# PT_SAT_Simplex.net
KiCad netlist of a schematic drawn in Altium Designer
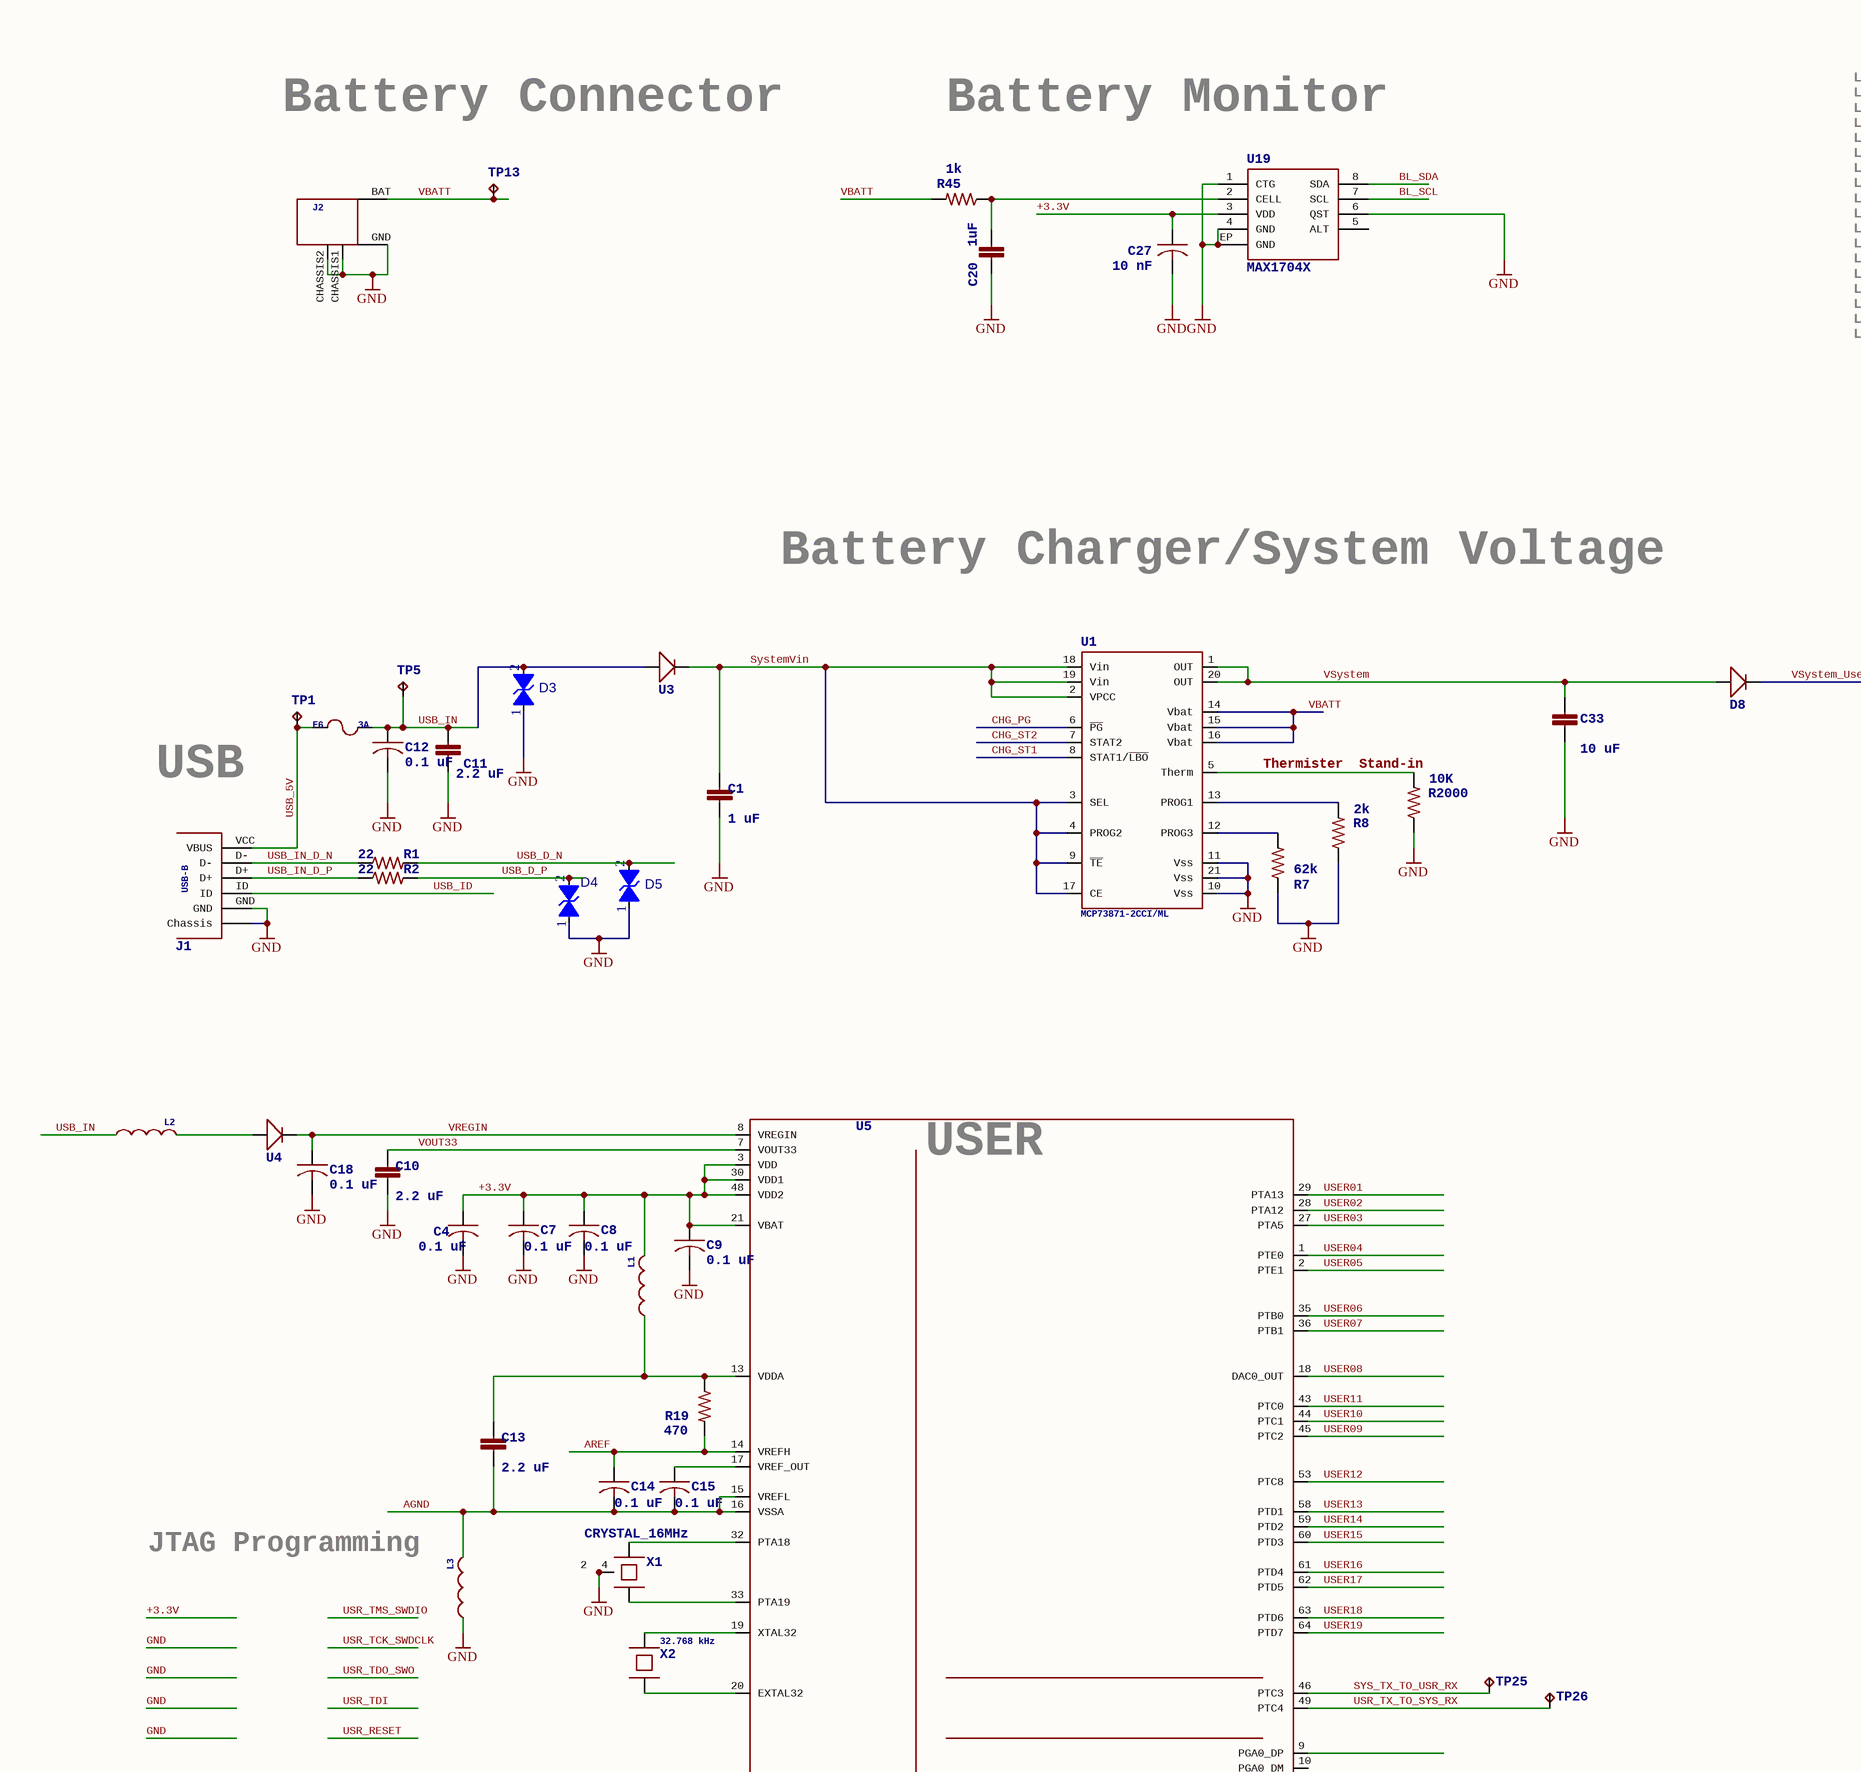
[diagram p0: PT_SAT_Simplex.SchDoc, top left]
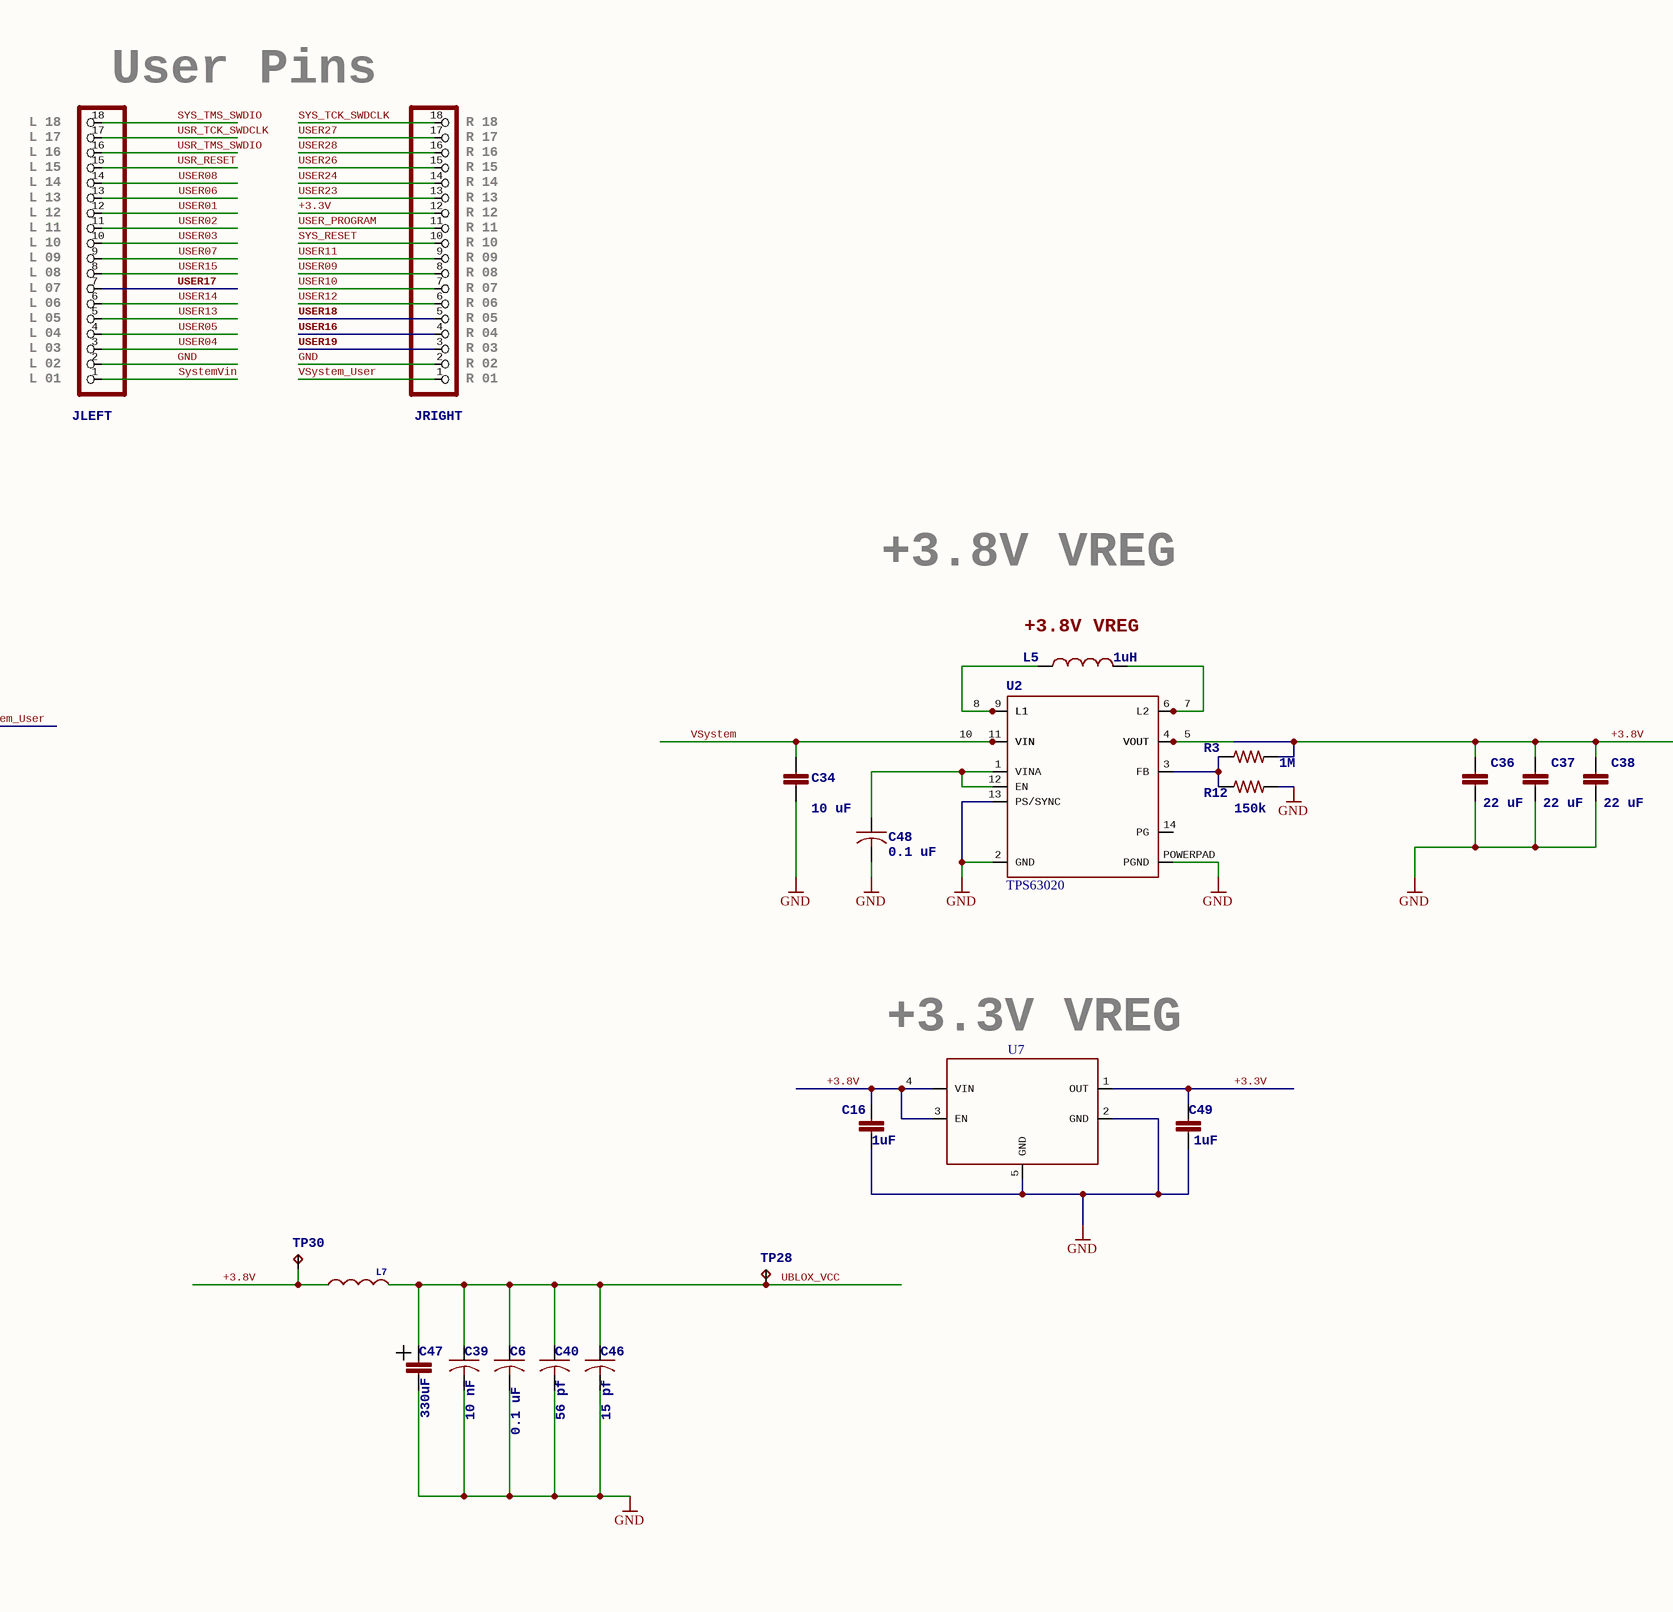
[diagram p1: PT_SAT_Simplex.SchDoc, top middle]
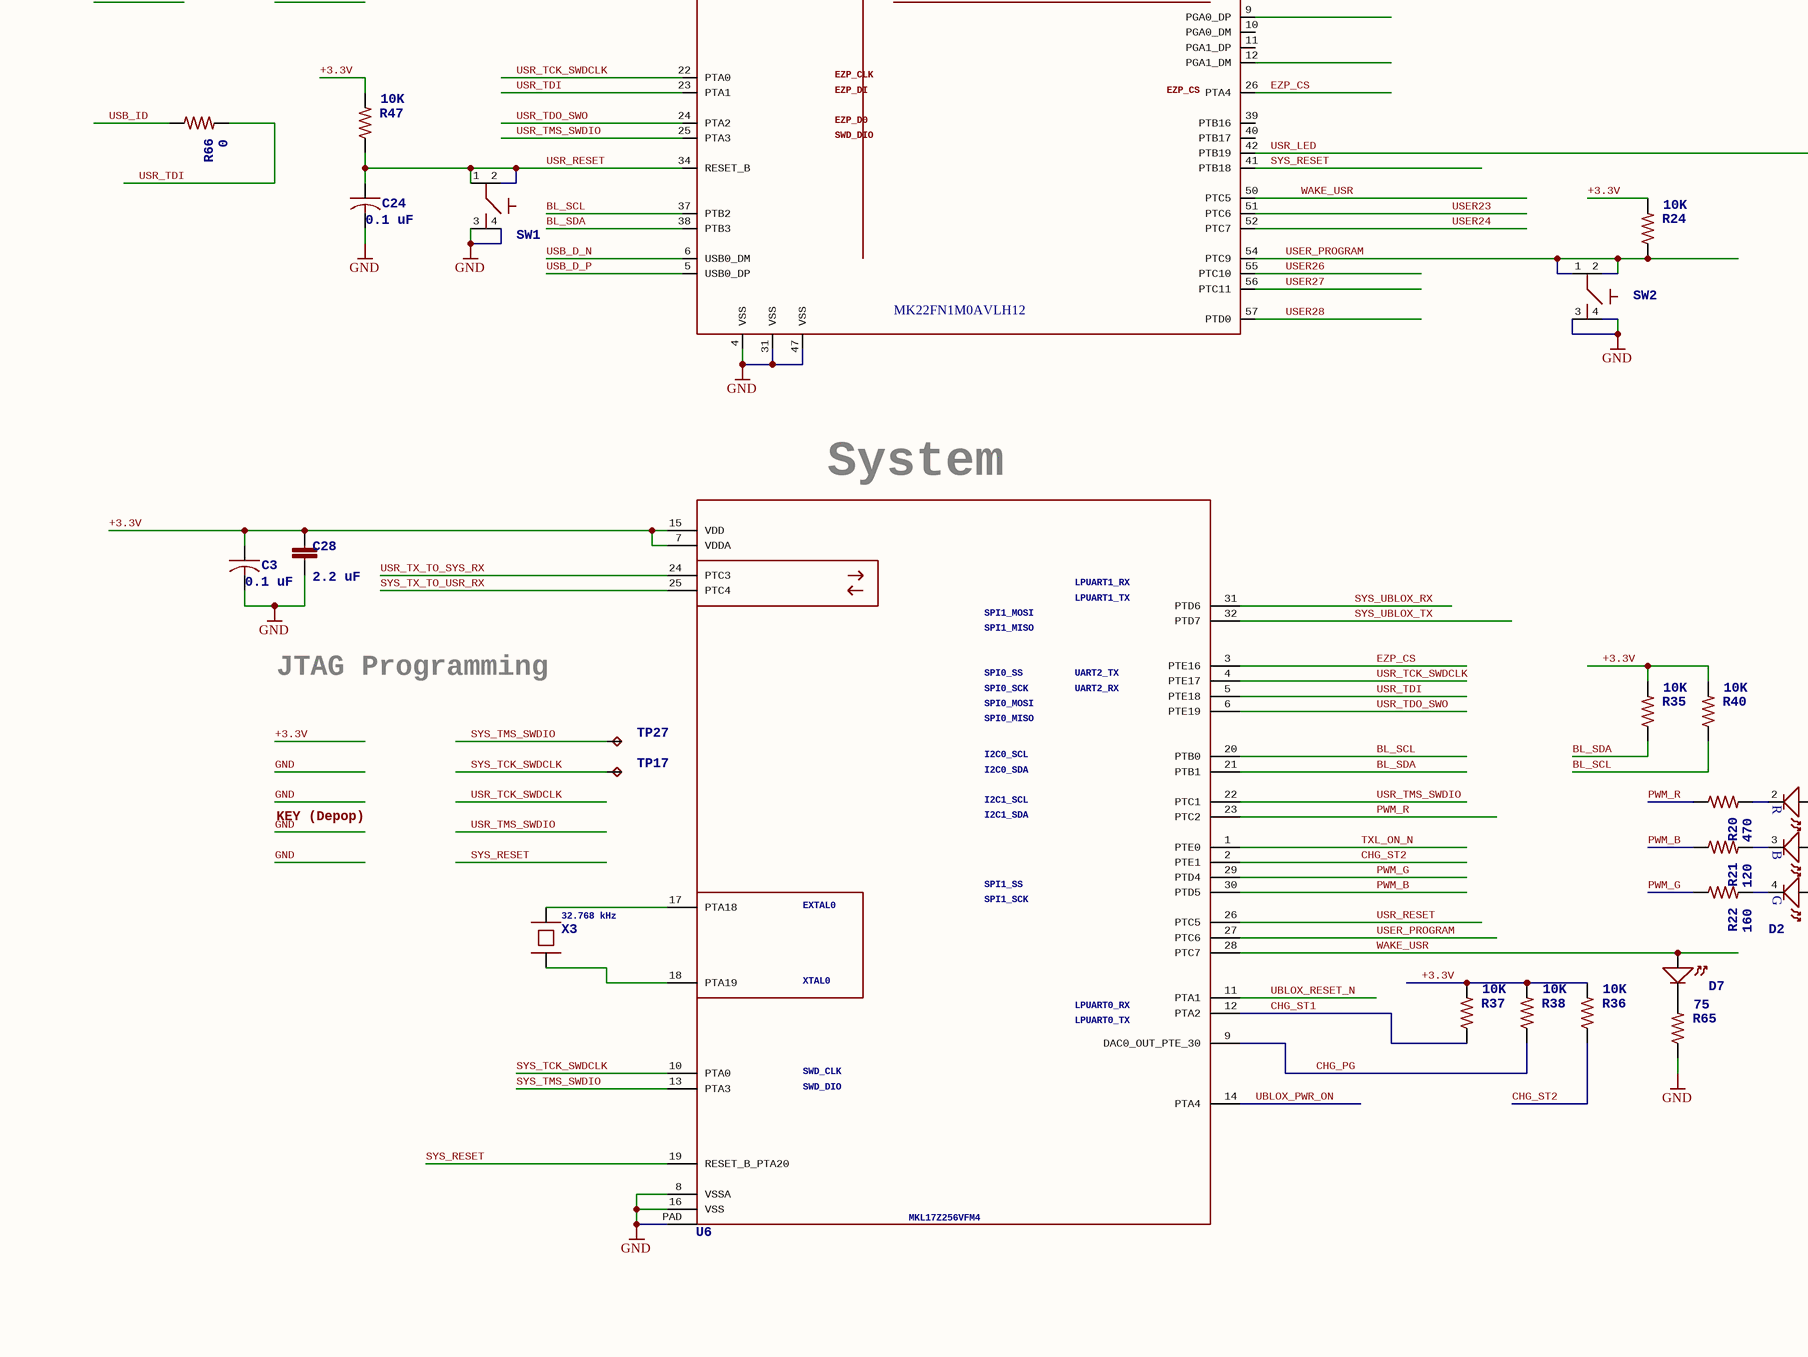
[diagram p2: PT_SAT_Simplex.SchDoc, bottom left]
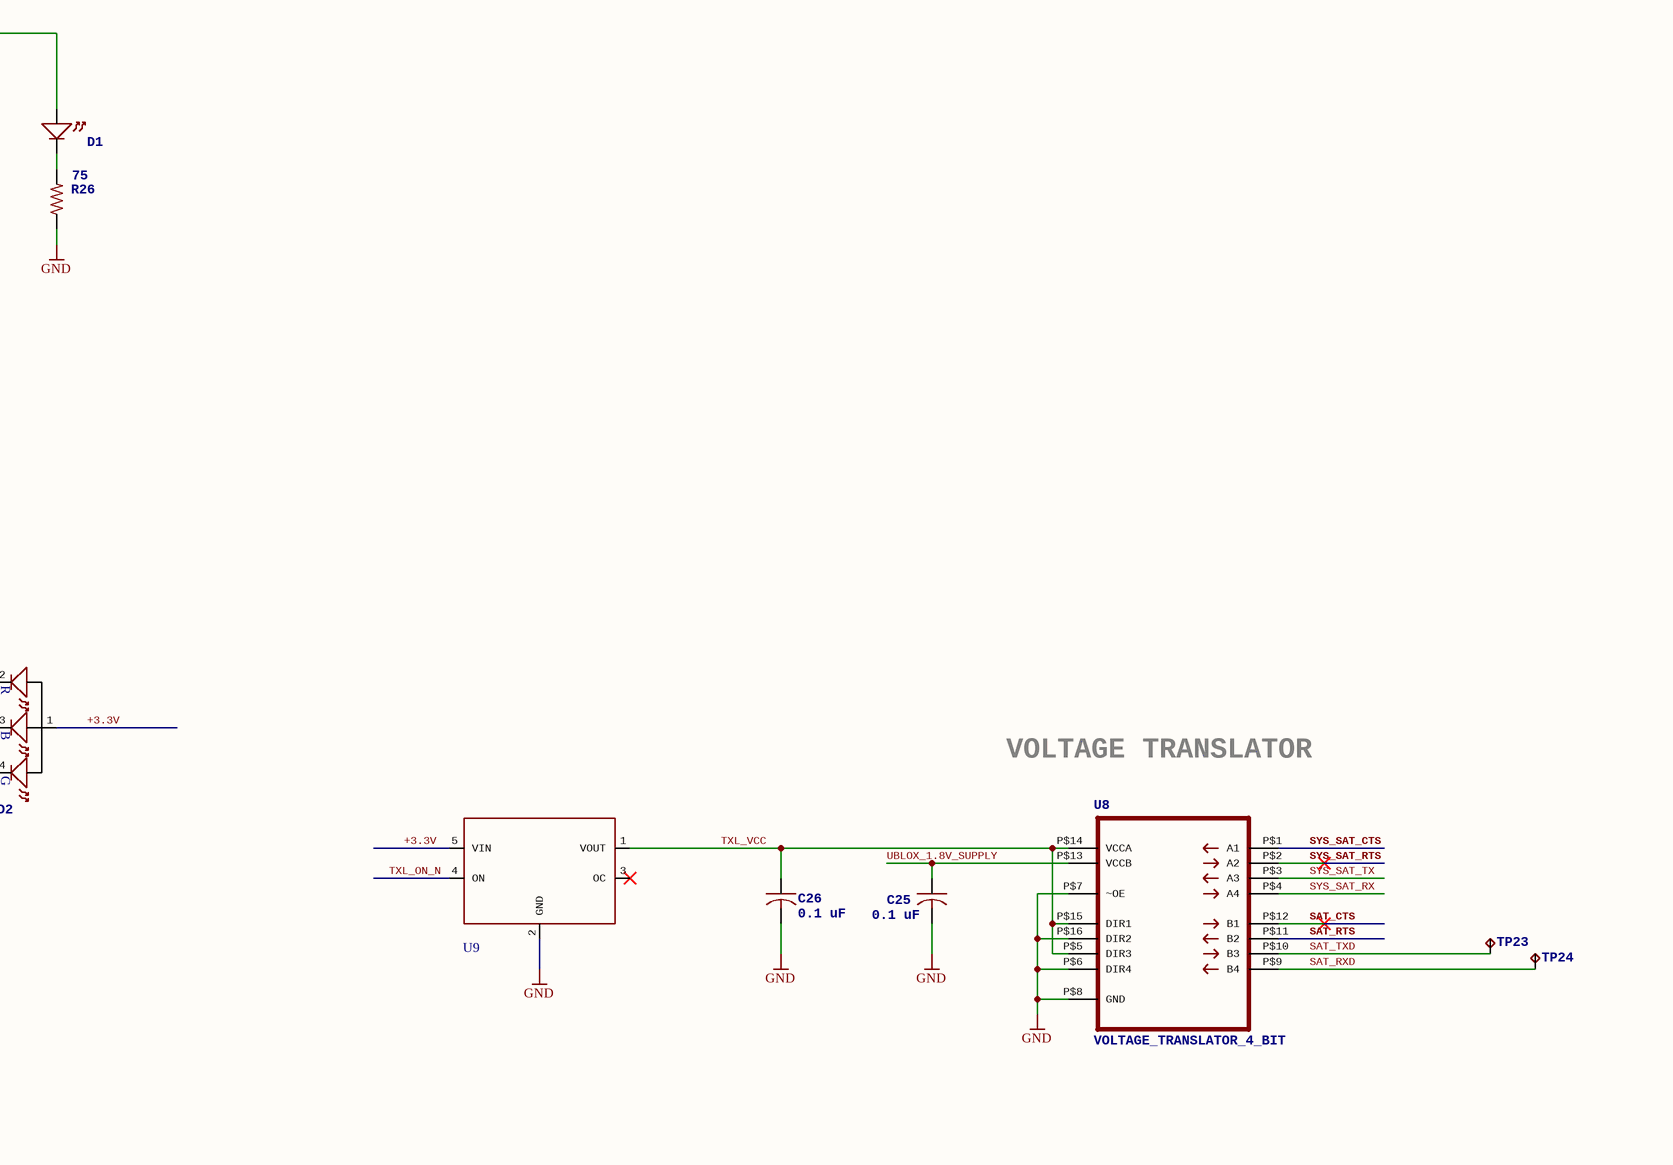
[diagram p3: PT_SAT_Simplex.SchDoc, bottom middle]
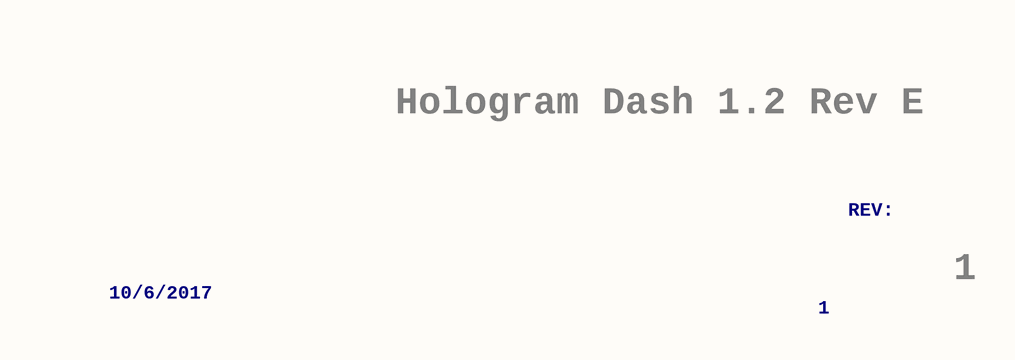
[diagram p4: PT_SAT_Simplex.SchDoc, bottom right]

(export (version "E")
  (design (tool "Eeschema 10.0.6"))
  (components
    (comp (ref "C1")
      (value "1 uF")
      (footprint "KON-SU260:CAP0603")
      (description "Capacitor, 1 uF, 0603")
      (fields (field (name "MPN") "GRM188R71C105KA12D") (field (name "MFG") "MURATA"))
      (libsource (lib "KON-SU260") (part "CAP1uF_0603"))
    )
    (comp (ref "C3")
      (value "0.1 uF")
      (footprint "KON-SU260:CAP0402")
      (description "CAPACITOR, 0.1 uF, 0402")
      (fields (field (name "MFG") "MURATA") (field (name "MPN") "GRM155R61C104KA88D"))
      (libsource (lib "KON-SU260") (part "CAP0.1uF_0402"))
    )
    (comp (ref "C4")
      (value "0.1 uF")
      (footprint "KON-SU260:CAP0402")
      (description "CAPACITOR, 0.1 uF, 0402")
      (fields (field (name "MFG") "MURATA") (field (name "MPN") "GRM155R61C104KA88D"))
      (libsource (lib "KON-SU260") (part "CAP0.1uF_0402"))
    )
    (comp (ref "C6")
      (value "0.1 uF")
      (footprint "KON-SU260:CAP0402")
      (description "CAPACITOR, 0.1 uF, 0402")
      (fields (field (name "MFG") "MURATA") (field (name "MPN") "GRM155R61C104KA88D"))
      (libsource (lib "KON-SU260") (part "CAP0.1uF_0402"))
    )
    (comp (ref "C7")
      (value "0.1 uF")
      (footprint "KON-SU260:CAP0402")
      (description "CAPACITOR, 0.1 uF, 0402")
      (fields (field (name "MFG") "MURATA") (field (name "MPN") "GRM155R61C104KA88D"))
      (libsource (lib "KON-SU260") (part "CAP0.1uF_0402"))
    )
    (comp (ref "C8")
      (value "0.1 uF")
      (footprint "KON-SU260:CAP0402")
      (description "CAPACITOR, 0.1 uF, 0402")
      (fields (field (name "MFG") "MURATA") (field (name "MPN") "GRM155R61C104KA88D"))
      (libsource (lib "KON-SU260") (part "CAP0.1uF_0402"))
    )
    (comp (ref "C9")
      (value "0.1 uF")
      (footprint "KON-SU260:CAP0402")
      (description "CAPACITOR, 0.1 uF, 0402")
      (fields (field (name "MFG") "MURATA") (field (name "MPN") "GRM155R61C104KA88D"))
      (libsource (lib "KON-SU260") (part "CAP0.1uF_0402"))
    )
    (comp (ref "C10")
      (value "2.2 uF")
      (footprint "KON-SU260:CAP0603")
      (description "Capacitor, 2.2 uF, 0603")
      (fields (field (name "MPN") "CL10A225MQ8NNNC") (field (name "MFG") "SAMSUNG"))
      (libsource (lib "KON-SU260") (part "CAP2.2uF_0603"))
    )
    (comp (ref "C11")
      (value "2.2 uF")
      (footprint "KON-SU260:CAP0603")
      (description "Capacitor, 2.2 uF, 0603")
      (fields (field (name "MPN") "CL10A225MQ8NNNC") (field (name "MFG") "SAMSUNG"))
      (libsource (lib "KON-SU260") (part "CAP2.2uF_0603"))
    )
    (comp (ref "C12")
      (value "0.1 uF")
      (footprint "KON-SU260:CAP0402")
      (description "CAPACITOR, 0.1 uF, 0402")
      (fields (field (name "MFG") "MURATA") (field (name "MPN") "GRM155R61C104KA88D"))
      (libsource (lib "KON-SU260") (part "CAP0.1uF_0402"))
    )
    (comp (ref "C13")
      (value "2.2 uF")
      (footprint "KON-SU260:CAP0603")
      (description "Capacitor, 2.2 uF, 0603")
      (fields (field (name "MPN") "CL10A225MQ8NNNC") (field (name "MFG") "SAMSUNG"))
      (libsource (lib "KON-SU260") (part "CAP2.2uF_0603"))
    )
    (comp (ref "C14")
      (value "0.1 uF")
      (footprint "KON-SU260:CAP0402")
      (description "CAPACITOR, 0.1 uF, 0402")
      (fields (field (name "MFG") "MURATA") (field (name "MPN") "GRM155R61C104KA88D"))
      (libsource (lib "KON-SU260") (part "CAP0.1uF_0402"))
    )
    (comp (ref "C15")
      (value "0.1 uF")
      (footprint "KON-SU260:CAP0402")
      (description "CAPACITOR, 0.1 uF, 0402")
      (fields (field (name "MFG") "MURATA") (field (name "MPN") "GRM155R61C104KA88D"))
      (libsource (lib "KON-SU260") (part "CAP0.1uF_0402"))
    )
    (comp (ref "C16")
      (value "1uF")
      (footprint "KON-SU260:CAP0402")
      (description "CAPACITOR, 1uF, 0402")
      (fields (field (name "MPN") "04026D105KAT2A") (field (name "MFG") "AVX"))
      (libsource (lib "KON-SU260") (part "CAP1uF_0402"))
    )
    (comp (ref "C18")
      (value "0.1 uF")
      (footprint "KON-SU260:CAP0402")
      (description "CAPACITOR, 0.1 uF, 0402")
      (fields (field (name "MFG") "MURATA") (field (name "MPN") "GRM155R61C104KA88D"))
      (libsource (lib "KON-SU260") (part "CAP0.1uF_0402"))
    )
    (comp (ref "C20")
      (value "1uF")
      (footprint "KON-SU260:CAP0402")
      (description "CAPACITOR, 1uF, 0402")
      (fields (field (name "MPN") "04026D105KAT2A") (field (name "MFG") "AVX"))
      (libsource (lib "KON-SU260") (part "CAP1uF_0402"))
    )
    (comp (ref "C24")
      (value "0.1 uF")
      (footprint "KON-SU260:CAP0402")
      (description "CAPACITOR, 0.1 uF, 0402")
      (fields (field (name "MFG") "MURATA") (field (name "MPN") "GRM155R61C104KA88D"))
      (libsource (lib "KON-SU260") (part "CAP0.1uF_0402"))
    )
    (comp (ref "C25")
      (value "0.1 uF")
      (footprint "KON-SU260:CAP0402")
      (description "CAPACITOR, 0.1 uF, 0402")
      (fields (field (name "MFG") "MURATA") (field (name "MPN") "GRM155R61C104KA88D"))
      (libsource (lib "KON-SU260") (part "CAP0.1uF_0402"))
    )
    (comp (ref "C26")
      (value "0.1 uF")
      (footprint "KON-SU260:CAP0402")
      (description "CAPACITOR, 0.1 uF, 0402")
      (fields (field (name "MFG") "MURATA") (field (name "MPN") "GRM155R61C104KA88D"))
      (libsource (lib "KON-SU260") (part "CAP0.1uF_0402"))
    )
    (comp (ref "C27")
      (value "10 nF")
      (footprint "KON-SU260:CAP0402")
      (description "CAPACITOR, 10 nF, 0402")
      (fields (field (name "MFG") "MURATA") (field (name "MPN") "GRM155R71C103KA01D"))
      (libsource (lib "KON-SU260") (part "CAP10nF_0402"))
    )
    (comp (ref "C28")
      (value "2.2 uF")
      (footprint "KON-SU260:CAP0603")
      (description "Capacitor, 2.2 uF, 0603")
      (fields (field (name "MPN") "CL10A225MQ8NNNC") (field (name "MFG") "SAMSUNG"))
      (libsource (lib "KON-SU260") (part "CAP2.2uF_0603"))
    )
    (comp (ref "C33")
      (value "10 uF")
      (footprint "KON-SU260:CAP0603")
      (description "Capacitor, 10 uF, 0603")
      (fields (field (name "MPN") "GRM188R60J106ME84D") (field (name "MFG") "Murata"))
      (libsource (lib "KON-SU260") (part "CAP10uF_0603"))
    )
    (comp (ref "C34")
      (value "10 uF")
      (footprint "KON-SU260:CAP0603")
      (description "Capacitor, 10 uF, 0603")
      (fields (field (name "MPN") "GRM188R60J106ME84D") (field (name "MFG") "Murata"))
      (libsource (lib "KON-SU260") (part "CAP10uF_0603"))
    )
    (comp (ref "C36")
      (value "22 uF")
      (footprint "KON-SU260:CAP0603")
      (description "Capacitor, 22 uF, 0603")
      (fields (field (name "MPN") "GRM188R60J226MEA0D") (field (name "MFG") "MURATA"))
      (libsource (lib "KON-SU260") (part "CAP22uF_0603"))
    )
    (comp (ref "C37")
      (value "22 uF")
      (footprint "KON-SU260:CAP0603")
      (description "Capacitor, 22 uF, 0603")
      (fields (field (name "MPN") "GRM188R60J226MEA0D") (field (name "MFG") "MURATA"))
      (libsource (lib "KON-SU260") (part "CAP22uF_0603"))
    )
    (comp (ref "C38")
      (value "22 uF")
      (footprint "KON-SU260:CAP0603")
      (description "Capacitor, 22 uF, 0603")
      (fields (field (name "MPN") "GRM188R60J226MEA0D") (field (name "MFG") "MURATA"))
      (libsource (lib "KON-SU260") (part "CAP22uF_0603"))
    )
    (comp (ref "C39")
      (value "10 nF")
      (footprint "KON-SU260:CAP0402")
      (description "CAPACITOR, 10 nF, 0402")
      (fields (field (name "MFG") "MURATA") (field (name "MPN") "GRM155R71C103KA01D"))
      (libsource (lib "KON-SU260") (part "CAP10nF_0402"))
    )
    (comp (ref "C40")
      (value "56 pf")
      (footprint "KON-SU260:CAP0402")
      (description "CAPACITOR, 56 pF, 0402")
      (fields (field (name "MFG") "KEMET") (field (name "MPN") "C0402C560J5GACTU"))
      (libsource (lib "KON-SU260") (part "CAP56pF_0402"))
    )
    (comp (ref "C46")
      (value "15 pf")
      (footprint "KON-SU260:CAP0402")
      (description "CAPACITOR, 15 pF, 0402")
      (fields (field (name "MFG") "AVX/ELCO") (field (name "MPN") "04025A150JAT2A"))
      (libsource (lib "KON-SU260") (part "CAP15pF_0402"))
    )
    (comp (ref "C47")
      (value "330uF")
      (footprint "KON-SU260:CAP1210POL")
      (description "Capacitor, 330 uF, 1210, Polarized Tantalum")
      (fields (field (name "MPN") "F950J337MBAAQ2") (field (name "MFG") "AVX"))
      (libsource (lib "KON-SU260") (part "CAP330uF_1210P"))
    )
    (comp (ref "C48")
      (value "0.1 uF")
      (footprint "KON-SU260:CAP0402")
      (description "CAPACITOR, 0.1 uF, 0402")
      (fields (field (name "MFG") "MURATA") (field (name "MPN") "GRM155R61C104KA88D"))
      (libsource (lib "KON-SU260") (part "CAP0.1uF_0402"))
    )
    (comp (ref "C49")
      (value "1uF")
      (footprint "KON-SU260:CAP0402")
      (description "CAPACITOR, 1uF, 0402")
      (fields (field (name "MPN") "04026D105KAT2A") (field (name "MFG") "AVX"))
      (libsource (lib "KON-SU260") (part "CAP1uF_0402"))
    )
    (comp (ref "D1")
      (value "LED_0402_VLMW")
      (footprint "LED_0402_VISHAY_VLMW")
      (description "LED, Vishay White 0402")
      (fields (field (name "MFG") "VISHAY") (field (name "MPN") "VLMW1500-GS08"))
      (libsource (lib "KON-SU260") (part "LED_0402_VLMW"))
    )
    (comp (ref "D2")
      (value "LED_RGB_1mm_sq")
      (footprint "LED-RGB-1X1")
      (description "LED, Tri-color, RGB, 1mm sq")
      (fields (field (name "MFG") "Rohm") (field (name "MPN") "SMLP34RGB2W3"))
      (libsource (lib "KON-SU260") (part "LED_RGB_1mm_sq"))
    )
    (comp (ref "D3")
      (value "~")
      (footprint "PESD_0402")
      (description "DIODE,ZENER VOLTAGE SUPPRESSOR,+/-14V")
      (fields (field (name "MFG") "Littlefuse") (field (name "MPN") "PESD0402-140"))
      (libsource (lib "KON-SU260") (part "PESD_14V"))
    )
    (comp (ref "D4")
      (value "~")
      (footprint "PESD_0402")
      (description "DIODE,ZENER VOLTAGE SUPPRESSOR,+/-14V")
      (fields (field (name "MFG") "Littlefuse") (field (name "MPN") "PESD0402-140"))
      (libsource (lib "KON-SU260") (part "PESD_14V"))
    )
    (comp (ref "D5")
      (value "~")
      (footprint "PESD_0402")
      (description "DIODE,ZENER VOLTAGE SUPPRESSOR,+/-14V")
      (fields (field (name "MFG") "Littlefuse") (field (name "MPN") "PESD0402-140"))
      (libsource (lib "KON-SU260") (part "PESD_14V"))
    )
    (comp (ref "D7")
      (value "LED_0402_VLMW")
      (footprint "LED_0402_VISHAY_VLMW")
      (description "LED, Vishay White 0402")
      (fields (field (name "MFG") "VISHAY") (field (name "MPN") "VLMW1500-GS08"))
      (libsource (lib "KON-SU260") (part "LED_0402_VLMW"))
    )
    (comp (ref "D8")
      (value "CDBQR0230L")
      (footprint "DIODE_0402")
      (description "Schottky Barrier Diode, 200 mA, 30 V, 0402 package")
      (fields (field (name "MFG") "Comchip"))
      (libsource (lib "KON-SU260") (part "DIODE_0402_200mA"))
    )
    (comp (ref "F6")
      (value "3A")
      (footprint "KON-SU260:RES0603")
      (description "Fuse, 3A, 0603")
      (fields (field (name "MFG") "Bourns") (field (name "MPN") "SF-0603S300-2"))
      (libsource (lib "KON-SU260") (part "FUSE_0603"))
    )
    (comp (ref "J1")
      (value "Micro USB B FCI 10118193")
      (footprint "USB_MICRO_FCI_10118193")
      (description "Connector, Micro USB B, FCI")
      (fields
        (field (name "MFG") "Amphenol FCI")
        (field (name "MPN") "10118193-0001LF")
        (field (name "USB-B") "USB-B")
      )
      (libsource (lib "KON-SU260") (part "USB_MICRO_B_FCI_10118193"))
    )
    (comp (ref "J2")
      (value "BAT_TERM_TOP_ENTRY")
      (footprint "JST-PH-2-Top")
      (description "Battery Connector JST-PH2 Top Entry")
      (fields (field (name "MPN") "B2B-PH-SM4-TB(LF)(SN)") (field (name "MFG") "JST"))
      (libsource (lib "KON-SU260") (part "BAT_TERM_TOP_ENTRY"))
    )
    (comp (ref "JLEFT")
      (value "22-28-4180")
      (footprint "KON-SU260:1X18")
      (description "Header, Male, 1x18, 0.1\"")
      (fields (field (name "MFG") "MOLEX"))
      (libsource (lib "KON-SU260") (part "PINHD-1X18"))
    )
    (comp (ref "JRIGHT")
      (value "22-28-4180")
      (footprint "KON-SU260:1X18")
      (description "Header, Male, 1x18, 0.1\"")
      (fields (field (name "MFG") "MOLEX"))
      (libsource (lib "KON-SU260") (part "PINHD-1X18"))
    )
    (comp (ref "L1")
      (value "FerriteBead_220ohm")
      (footprint "KON-SU260:RES0603")
      (description "FerriteBead, 220ohm")
      (fields (field (name "MPN") "BLM18AG121SN1D") (field (name "MFG") "Murata"))
      (libsource (lib "KON-SU260") (part "FerriteBead_220ohm"))
    )
    (comp (ref "L2")
      (value "FerriteBead_220ohm")
      (footprint "KON-SU260:RES0603")
      (description "FerriteBead, 220ohm")
      (fields (field (name "MPN") "BLM18AG121SN1D") (field (name "MFG") "Murata"))
      (libsource (lib "KON-SU260") (part "FerriteBead_220ohm"))
    )
    (comp (ref "L3")
      (value "FerriteBead_220ohm")
      (footprint "KON-SU260:RES0603")
      (description "FerriteBead, 220ohm")
      (fields (field (name "MPN") "BLM18AG121SN1D") (field (name "MFG") "Murata"))
      (libsource (lib "KON-SU260") (part "FerriteBead_220ohm"))
    )
    (comp (ref "L5")
      (value "1uH")
      (footprint "COILCRAFT_XFL4020")
      (description "Inductor, 1 uH, Coilcraft")
      (fields (field (name "MPN") "XFL4020-102MEC") (field (name "MFG") "Coilcraft"))
      (libsource (lib "KON-SU260") (part "INDUCTOR_1UH_XFL4020-102MEC"))
    )
    (comp (ref "L7")
      (value "FerriteBead_220ohm")
      (footprint "KON-SU260:RES0603")
      (description "FerriteBead, 220ohm")
      (fields (field (name "MPN") "BLM18AG121SN1D") (field (name "MFG") "Murata"))
      (libsource (lib "KON-SU260") (part "FerriteBead_220ohm"))
    )
    (comp (ref "R1")
      (value "22")
      (footprint "KON-SU260:RES0402")
      (description "Resistor, 22 ohm, 0402 case, 1%")
      (fields (field (name "MFG") "YAEGO") (field (name "MPN") "RC0402FR-0722RL"))
      (libsource (lib "KON-SU260") (part "RES22R_0402"))
    )
    (comp (ref "R2")
      (value "22")
      (footprint "KON-SU260:RES0402")
      (description "Resistor, 22 ohm, 0402 case, 1%")
      (fields (field (name "MFG") "YAEGO") (field (name "MPN") "RC0402FR-0722RL"))
      (libsource (lib "KON-SU260") (part "RES22R_0402"))
    )
    (comp (ref "R3")
      (value "1M")
      (footprint "KON-SU260:RES0402")
      (description "Resistor, 1M ohm, 0402 case, 1%")
      (fields (field (name "MFG") "YAEGO") (field (name "MPN") "RC0402FR-071ML"))
      (libsource (lib "KON-SU260") (part "RES1M_0402"))
    )
    (comp (ref "R7")
      (value "62k")
      (footprint "KON-SU260:RES0402")
      (description "Resistor, 62K ohm, 0402 case")
      (fields (field (name "MFG") "YAEGO") (field (name "MPN") "RC0402FR-0762KL"))
      (libsource (lib "KON-SU260") (part "RES62K_0402_1"))
    )
    (comp (ref "R8")
      (value "2k")
      (footprint "KON-SU260:RES0402")
      (description "Resistor, 2K ohm, 0402 case")
      (fields (field (name "MFG") "YAEGO") (field (name "MPN") "RC0402FR-072KL"))
      (libsource (lib "KON-SU260") (part "RES2K_0402"))
    )
    (comp (ref "R12")
      (value "150k")
      (footprint "KON-SU260:RES0402")
      (description "Res, 150k ohm, 0402 case, 1%")
      (fields (field (name "MFG") "YAEGO") (field (name "MPN") "RC0402FR-07150KL"))
      (libsource (lib "KON-SU260") (part "RES150K_0402"))
    )
    (comp (ref "R19")
      (value "470")
      (footprint "KON-SU260:RES0402")
      (description "Resistor, 470 ohm, 0402 case, 1%")
      (fields (field (name "MFG") "PANASONIC") (field (name "MPN") "ERJ-2GEJ471X"))
      (libsource (lib "KON-SU260") (part "RES470R_0402"))
    )
    (comp (ref "R20")
      (value "470")
      (footprint "KON-SU260:RES0402")
      (description "Resistor, 470 ohm, 0402 case, 1%")
      (fields (field (name "MFG") "PANASONIC") (field (name "MPN") "ERJ-2GEJ471X"))
      (libsource (lib "KON-SU260") (part "RES470R_0402"))
    )
    (comp (ref "R21")
      (value "120")
      (footprint "KON-SU260:RES0402")
      (description "Resistor, 120 ohm, 0402 case, 1%")
      (fields (field (name "MFG") "PANASONIC") (field (name "MPN") "ERJ-2GEJ121X"))
      (libsource (lib "KON-SU260") (part "RES120R_0402"))
    )
    (comp (ref "R22")
      (value "160")
      (footprint "KON-SU260:RES0402")
      (description "Resistor, 160 ohm, 0402 case, 1%")
      (fields (field (name "MFG") "PANASONIC") (field (name "MPN") "ERJ-2GEJ161X"))
      (libsource (lib "KON-SU260") (part "RES160R_0402"))
    )
    (comp (ref "R24")
      (value "10K")
      (footprint "KON-SU260:RES0402")
      (description "Resistor, 10k ohm, 0402")
      (fields (field (name "MFG") "YAEGO") (field (name "MPN") "RC0402JR-0710KL"))
      (libsource (lib "KON-SU260") (part "RES10K_0402"))
    )
    (comp (ref "R26")
      (value "75")
      (footprint "KON-SU260:RES0402")
      (description "Resistor, 75 ohm, 0402, 1%")
      (fields (field (name "MFG") "YAEGO") (field (name "MPN") "RC0402FR-0775RL"))
      (libsource (lib "KON-SU260") (part "RES75R_0402"))
    )
    (comp (ref "R35")
      (value "10K")
      (footprint "KON-SU260:RES0402")
      (description "Resistor, 10k ohm, 0402")
      (fields (field (name "MFG") "YAEGO") (field (name "MPN") "RC0402JR-0710KL"))
      (libsource (lib "KON-SU260") (part "RES10K_0402"))
    )
    (comp (ref "R36")
      (value "10K")
      (footprint "KON-SU260:RES0402")
      (description "Resistor, 10k ohm, 0402")
      (fields (field (name "MFG") "YAEGO") (field (name "MPN") "RC0402JR-0710KL"))
      (libsource (lib "KON-SU260") (part "RES10K_0402"))
    )
    (comp (ref "R37")
      (value "10K")
      (footprint "KON-SU260:RES0402")
      (description "Resistor, 10k ohm, 0402")
      (fields (field (name "MFG") "YAEGO") (field (name "MPN") "RC0402JR-0710KL"))
      (libsource (lib "KON-SU260") (part "RES10K_0402"))
    )
    (comp (ref "R38")
      (value "10K")
      (footprint "KON-SU260:RES0402")
      (description "Resistor, 10k ohm, 0402")
      (fields (field (name "MFG") "YAEGO") (field (name "MPN") "RC0402JR-0710KL"))
      (libsource (lib "KON-SU260") (part "RES10K_0402"))
    )
    (comp (ref "R40")
      (value "10K")
      (footprint "KON-SU260:RES0402")
      (description "Resistor, 10k ohm, 0402")
      (fields (field (name "MFG") "YAEGO") (field (name "MPN") "RC0402JR-0710KL"))
      (libsource (lib "KON-SU260") (part "RES10K_0402"))
    )
    (comp (ref "R45")
      (value "1k")
      (footprint "KON-SU260:RES0402")
      (description "Resistor, 1k, 0402 case, 1%")
      (fields (field (name "MFG") "YAEGO") (field (name "MPN") "RC0402JR-071KL"))
      (libsource (lib "KON-SU260") (part "RES1K_0402"))
    )
    (comp (ref "R47")
      (value "10K")
      (footprint "KON-SU260:RES0402")
      (description "Resistor, 10k ohm, 0402")
      (fields (field (name "MFG") "YAEGO") (field (name "MPN") "RC0402JR-0710KL"))
      (libsource (lib "KON-SU260") (part "RES10K_0402"))
    )
    (comp (ref "R65")
      (value "75")
      (footprint "KON-SU260:RES0402")
      (description "Resistor, 75 ohm, 0402, 1%")
      (fields (field (name "MFG") "YAEGO") (field (name "MPN") "RC0402FR-0775RL"))
      (libsource (lib "KON-SU260") (part "RES75R_0402"))
    )
    (comp (ref "R66")
      (value "0")
      (footprint "KON-SU260:RES0402")
      (description "Resistor, 0 ohm, 0402")
      (fields (field (name "MFG") "PANASONIC") (field (name "MPN") "ERJ-2GE0R00X"))
      (libsource (lib "KON-SU260") (part "RES0R_0402"))
    )
    (comp (ref "R2000")
      (value "10K")
      (footprint "KON-SU260:RES0402")
      (description "Resistor, 10k ohm, 0402")
      (fields (field (name "MFG") "YAEGO") (field (name "MPN") "RC0402JR-0710KL"))
      (libsource (lib "KON-SU260") (part "RES10K_0402"))
    )
    (comp (ref "SW1")
      (value "SWITCH_PTS810")
      (footprint "SWITCH_PTS810")
      (description "Switch, C&K, PTS810")
      (fields (field (name "MFG") "C&K Components") (field (name "MPN") "PTS810 SJM 250 SMTR LFS"))
      (libsource (lib "KON-SU260") (part "SWITCH_PTS810"))
    )
    (comp (ref "SW2")
      (value "SWITCH_PTS810")
      (footprint "SWITCH_PTS810")
      (description "Switch, C&K, PTS810")
      (fields (field (name "MFG") "C&K Components") (field (name "MPN") "PTS810 SJM 250 SMTR LFS"))
      (libsource (lib "KON-SU260") (part "SWITCH_PTS810"))
    )
    (comp (ref "TP1")
      (value "TPTP08R")
      (footprint "TP08R")
      (description "Test pad")
      (libsource (lib "KON-SU260") (part "TPTP08R"))
    )
    (comp (ref "TP5")
      (value "TPTP08R")
      (footprint "TP08R")
      (description "Test pad")
      (libsource (lib "KON-SU260") (part "TPTP08R"))
    )
    (comp (ref "TP13")
      (value "TPTP08R")
      (footprint "TP08R")
      (description "Test pad")
      (libsource (lib "KON-SU260") (part "TPTP08R"))
    )
    (comp (ref "TP17")
      (value "TPTP08R")
      (footprint "TP08R")
      (description "Test pad")
      (libsource (lib "KON-SU260") (part "TPTP08R"))
    )
    (comp (ref "TP23")
      (value "TPTP08R")
      (footprint "TP08R")
      (description "Test pad")
      (libsource (lib "KON-SU260") (part "TPTP08R"))
    )
    (comp (ref "TP24")
      (value "TPTP08R")
      (footprint "TP08R")
      (description "Test pad")
      (libsource (lib "KON-SU260") (part "TPTP08R"))
    )
    (comp (ref "TP25")
      (value "TPTP08R")
      (footprint "TP08R")
      (description "Test pad")
      (libsource (lib "KON-SU260") (part "TPTP08R"))
    )
    (comp (ref "TP26")
      (value "TPTP08R")
      (footprint "TP08R")
      (description "Test pad")
      (libsource (lib "KON-SU260") (part "TPTP08R"))
    )
    (comp (ref "TP27")
      (value "TPTP08R")
      (footprint "TP08R")
      (description "Test pad")
      (libsource (lib "KON-SU260") (part "TPTP08R"))
    )
    (comp (ref "TP28")
      (value "TPTP08R")
      (footprint "TP08R")
      (description "Test pad")
      (libsource (lib "KON-SU260") (part "TPTP08R"))
    )
    (comp (ref "TP30")
      (value "TPTP08R")
      (footprint "TP08R")
      (description "Test pad")
      (libsource (lib "KON-SU260") (part "TPTP08R"))
    )
    (comp (ref "U1")
      (value "MICROCHIP_73871")
      (footprint "QFN50P400X400X80_20_pin")
      (description "Stand-alone Load Sharing and LiPo Battery Charge management controller")
      (fields (field (name "MFG") "MICROCHIP") (field (name "MPN") "MCP73871-2CCI/ML"))
      (libsource (lib "KON-SU260") (part "MICROCHIP_73871"))
    )
    (comp (ref "U2")
      (value "TPS63020")
      (footprint "QFN-14-POWERPAD3X4DSJ")
      (description "Regulator, Boost Buck, Adjustable, 3A")
      (fields (field (name "MFG") "TI") (field (name "MPN") "TPS63020DSJ"))
      (libsource (lib "KON-SU260") (part "TPS63020"))
    )
    (comp (ref "U3")
      (value "CDBQR0230L")
      (footprint "SODFL350X99-2N")
      (description "Schottky Barrier Diode, 1.5 A, 30 V, 0402 package")
      (fields
        (field (name "MFG") "Toshiba Semiconductor and Storage")
        (field (name "MPN") "CRS08(TE85L,Q,M)")
      )
      (libsource (lib "KON-SU260") (part "DIODE_SOD123F_1A"))
    )
    (comp (ref "U4")
      (value "CDBQR0230L")
      (footprint "SODFL350X99-2N")
      (description "Schottky Barrier Diode, 1.5 A, 30 V, 0402 package")
      (fields
        (field (name "MFG") "Toshiba Semiconductor and Storage")
        (field (name "MPN") "CRS08(TE85L,Q,M)")
      )
      (libsource (lib "KON-SU260") (part "DIODE_SOD123F_1A"))
    )
    (comp (ref "U5")
      (value "MK22FN1M0VLH12")
      (footprint "KON-SU260:LQFP-64N")
      (description "ARM® Cortex®-M4 Kinetis K20 Microcontroller IC 32-Bit 120MHz 1MB (1M x 8) FLASH 64-LQFP (10x10)")
      (fields (field (name "MPN") "MK22FN1M0AVLH12") (field (name "MFG") "Freescale"))
      (libsource (lib "KON-SU260") (part "MK22FN1M0VLH12"))
    )
    (comp (ref "U6")
      (value "FREESCALE_MKL17Z256VFM4")
      (footprint "KON-SU260:QFN50P50")
      (description "Microprocessor, Freescale, MKL17Z256VFM4")
      (fields
        (field (name "MFG") "FREESCALE")
        (field (name "MPN") "MKL17Z256VFM4")
        (field (name "SPI0_SS") "SPI0_SS")
        (field (name "UART2_TX") "UART2_TX")
        (field (name "SPI0_SCK") "SPI0_SCK")
        (field (name "UART2_RX") "UART2_RX")
        (field (name "SPI0_MOSI") "SPI0_MOSI")
        (field (name "SPI0_MISO") "SPI0_MISO")
        (field (name "SWD_CLK") "SWD_CLK")
        (field (name "SWD_DIO") "SWD_DIO")
        (field (name "EXTAL0") "EXTAL0")
        (field (name "XTAL0") "XTAL0")
        (field (name "LPUART0_RX") "LPUART0_RX")
        (field (name "LPUART0_TX") "LPUART0_TX")
        (field (name "I2C0_SCL") "I2C0_SCL")
        (field (name "I2C0_SDA") "I2C0_SDA")
        (field (name "LPUART1_TX") "LPUART1_TX")
        (field (name "SPI1_SS") "SPI1_SS")
        (field (name "SPI1_SCK") "SPI1_SCK")
        (field (name "SPI1_MOSI") "SPI1_MOSI")
        (field (name "MKL17Z256VFM4") "MKL17Z256VFM4")
        (field (name "SPI1_MISO") "SPI1_MISO")
        (field (name "I2C1_SCL") "I2C1_SCL")
        (field (name "I2C1_SDA") "I2C1_SDA")
        (field (name "LPUART1_RX") "LPUART1_RX")
      )
      (libsource (lib "KON-SU260") (part "FREESCALE_MKL17Z256VFM4"))
    )
    (comp (ref "U7")
      (value "~")
      (footprint "KON-SU260:XDFN-4")
      (description "IC Regulator, LDO 3.3V 0.5A, 4XDFN")
      (fields (field (name "MFG") "On Semi") (field (name "MPN") "NCP177AMX330TCG"))
      (libsource (lib "KON-SU260") (part "NCP177-D"))
    )
    (comp (ref "U8")
      (value "VOLTAGE_TRANSLATOR_4_BIT")
      (footprint "UQFN_16")
      (description "IC, Voltage Translator, 4-bit")
      (fields (field (name "MFG") "TI") (field (name "MPN") "SN74AVC4T774RSVR"))
      (libsource (lib "KON-SU260") (part "VOLTAGE_TRANSLATOR_4_BIT"))
    )
    (comp (ref "U9")
      (value "~")
      (footprint "KON-SU260:SC70-5")
      (description "IC, Current-limited  Load Switch, Active High")
      (fields (field (name "MFG") "Texas Instruments") (field (name "MPN") "TPS22945DCKR"))
      (libsource (lib "KON-SU260") (part "TPS22945"))
    )
    (comp (ref "U19")
      (value "MAX1704X")
      (footprint "TDFN-8")
      (description "MAX17043/MAX17044: Battery Fuel Guage (43 is 1cell, 44 is 2cell)")
      (fields (field (name "MFG") "Maxim") (field (name "MPN") "MAX17043G+U"))
      (libsource (lib "KON-SU260") (part "MAX1704X"))
    )
    (comp (ref "X1")
      (value "CRYSTAL_16MHz")
      (footprint "CRYSTAL-SMD-2X1.6")
      (description "Crystal SMD, 16 MHz")
      (fields (field (name "MPN") "CX2016DB16000D0WZRC1") (field (name "MFG") "AVX"))
      (libsource (lib "KON-SU260") (part "CRYSTAL_16MHz"))
    )
    (comp (ref "X2")
      (value "32.768 kHz")
      (footprint "CRYSTAL_ABS05")
      (description "32.768kHz ±20ppm Crystal 12.5pF 90 kOhm -40°C ~ 85°C Surface Mount 2-SMD")
      (fields (field (name "MFG") "Abracon") (field (name "MPN") "ABS05-32.768KHZ-T"))
      (libsource (lib "KON-SU260") (part "CRYSTAL_32.768K_ABS05"))
    )
    (comp (ref "X3")
      (value "32.768 kHz")
      (footprint "CRYSTAL_ABS05")
      (description "32.768kHz ±20ppm Crystal 12.5pF 90 kOhm -40°C ~ 85°C Surface Mount 2-SMD")
      (fields (field (name "MFG") "Abracon") (field (name "MPN") "ABS05-32.768KHZ-T"))
      (libsource (lib "KON-SU260") (part "CRYSTAL_32.768K_ABS05"))
    )
  )
  (nets
    (net (code "1") (name "/+3.3V") (class "Default")
      (node (ref "C27") (pin "1") (pinfunction "1_1") (pintype "passive"))
      (node (ref "C28") (pin "1") (pinfunction "1_1") (pintype "passive"))
      (node (ref "C3") (pin "1") (pinfunction "1_1") (pintype "passive"))
      (node (ref "C4") (pin "1") (pinfunction "1_1") (pintype "passive"))
      (node (ref "C49") (pin "1") (pinfunction "1_1") (pintype "passive"))
      (node (ref "C7") (pin "1") (pinfunction "1_1") (pintype "passive"))
      (node (ref "C8") (pin "1") (pinfunction "1_1") (pintype "passive"))
      (node (ref "C9") (pin "1") (pinfunction "1_1") (pintype "passive"))
      (node (ref "D2") (pin "1") (pinfunction "Common_ANODE_1") (pintype "passive"))
      (node (ref "JRIGHT") (pin "12") (pinfunction "12_12") (pintype "passive"))
      (node (ref "L1") (pin "1") (pinfunction "P$1_1") (pintype "passive"))
      (node (ref "R24") (pin "2") (pinfunction "2_2") (pintype "passive"))
      (node (ref "R35") (pin "2") (pinfunction "2_2") (pintype "passive"))
      (node (ref "R36") (pin "2") (pinfunction "2_2") (pintype "passive"))
      (node (ref "R37") (pin "2") (pinfunction "2_2") (pintype "passive"))
      (node (ref "R38") (pin "2") (pinfunction "2_2") (pintype "passive"))
      (node (ref "R40") (pin "2") (pinfunction "2_2") (pintype "passive"))
      (node (ref "R47") (pin "2") (pinfunction "2_2") (pintype "passive"))
      (node (ref "U19") (pin "3") (pinfunction "VDD_3") (pintype "passive"))
      (node (ref "U5") (pin "21") (pinfunction "VBAT_21") (pintype "passive"))
      (node (ref "U5") (pin "3") (pinfunction "VDD_3") (pintype "passive"))
      (node (ref "U5") (pin "30") (pinfunction "VDD1_30") (pintype "passive"))
      (node (ref "U5") (pin "48") (pinfunction "VDD2_48") (pintype "passive"))
      (node (ref "U6") (pin "15") (pinfunction "VDD_15") (pintype "passive"))
      (node (ref "U6") (pin "7") (pinfunction "VDDA_7") (pintype "passive"))
      (node (ref "U7") (pin "1") (pinfunction "OUT_1") (pintype "passive"))
      (node (ref "U9") (pin "5") (pinfunction "VIN_5") (pintype "passive"))
    )
    (net (code "2") (name "/+3.8V") (class "Default")
      (node (ref "C16") (pin "1") (pinfunction "1_1") (pintype "passive"))
      (node (ref "C36") (pin "1") (pinfunction "1_1") (pintype "passive"))
      (node (ref "C37") (pin "1") (pinfunction "1_1") (pintype "passive"))
      (node (ref "C38") (pin "1") (pinfunction "1_1") (pintype "passive"))
      (node (ref "L7") (pin "2") (pinfunction "P$2_2") (pintype "passive"))
      (node (ref "R3") (pin "2") (pinfunction "2_2") (pintype "passive"))
      (node (ref "TP30") (pin "TP") (pinfunction "TP_TP") (pintype "passive"))
      (node (ref "U2") (pin "4") (pinfunction "VOUT_4") (pintype "passive"))
      (node (ref "U2") (pin "5") (pinfunction "VOUT_5") (pintype "passive"))
      (node (ref "U7") (pin "3") (pinfunction "EN_3") (pintype "passive"))
      (node (ref "U7") (pin "4") (pinfunction "VIN_4") (pintype "passive"))
    )
    (net (code "3") (name "/AGND") (class "Default")
      (node (ref "C13") (pin "2") (pinfunction "2_2") (pintype "passive"))
      (node (ref "C14") (pin "2") (pinfunction "2_2") (pintype "passive"))
      (node (ref "C15") (pin "2") (pinfunction "2_2") (pintype "passive"))
      (node (ref "L3") (pin "1") (pinfunction "P$1_1") (pintype "passive"))
      (node (ref "U5") (pin "15") (pinfunction "VREFL_15") (pintype "passive"))
      (node (ref "U5") (pin "16") (pinfunction "VSSA_16") (pintype "passive"))
    )
    (net (code "4") (name "/AREF") (class "Default")
      (node (ref "C14") (pin "1") (pinfunction "1_1") (pintype "passive"))
      (node (ref "R19") (pin "2") (pinfunction "2_2") (pintype "passive"))
      (node (ref "U5") (pin "14") (pinfunction "VREFH_14") (pintype "passive"))
    )
    (net (code "5") (name "/BL_SCL") (class "Default")
      (node (ref "R40") (pin "1") (pinfunction "1_1") (pintype "passive"))
      (node (ref "U19") (pin "7") (pinfunction "SCL_7") (pintype "passive"))
      (node (ref "U5") (pin "37") (pinfunction "PTB2_37") (pintype "passive"))
      (node (ref "U6") (pin "20") (pinfunction "PTB0_20") (pintype "passive"))
    )
    (net (code "6") (name "/BL_SDA") (class "Default")
      (node (ref "R35") (pin "1") (pinfunction "1_1") (pintype "passive"))
      (node (ref "U19") (pin "8") (pinfunction "SDA_8") (pintype "passive"))
      (node (ref "U5") (pin "38") (pinfunction "PTB3_38") (pintype "passive"))
      (node (ref "U6") (pin "21") (pinfunction "PTB1_21") (pintype "passive"))
    )
    (net (code "7") (name "/CHG_PG") (class "Default")
      (node (ref "R38") (pin "1") (pinfunction "1_1") (pintype "passive"))
      (node (ref "U1") (pin "6") (pinfunction "~{PG}_6") (pintype "passive"))
      (node (ref "U6") (pin "9") (pinfunction "DAC0_OUT_PTE_30_9") (pintype "passive"))
    )
    (net (code "8") (name "/CHG_ST1") (class "Default")
      (node (ref "R37") (pin "1") (pinfunction "1_1") (pintype "passive"))
      (node (ref "U1") (pin "8") (pinfunction "STAT1/~{LBO}_8") (pintype "passive"))
      (node (ref "U6") (pin "12") (pinfunction "PTA2_12") (pintype "passive"))
    )
    (net (code "9") (name "/CHG_ST2") (class "Default")
      (node (ref "R36") (pin "1") (pinfunction "1_1") (pintype "passive"))
      (node (ref "U1") (pin "7") (pinfunction "STAT2_7") (pintype "passive"))
      (node (ref "U6") (pin "2") (pinfunction "PTE1_2") (pintype "passive"))
    )
    (net (code "10") (name "/EZP_CS") (class "Default")
      (node (ref "U5") (pin "26") (pinfunction "PTA4_26") (pintype "passive"))
      (node (ref "U6") (pin "3") (pinfunction "PTE16_3") (pintype "passive"))
    )
    (net (code "11") (name "/PWM_B") (class "Default")
      (node (ref "R21") (pin "1") (pinfunction "1_1") (pintype "passive"))
      (node (ref "U6") (pin "30") (pinfunction "PTD5_30") (pintype "passive"))
    )
    (net (code "12") (name "/PWM_G") (class "Default")
      (node (ref "R22") (pin "1") (pinfunction "1_1") (pintype "passive"))
      (node (ref "U6") (pin "29") (pinfunction "PTD4_29") (pintype "passive"))
    )
    (net (code "13") (name "/PWM_R") (class "Default")
      (node (ref "R20") (pin "1") (pinfunction "1_1") (pintype "passive"))
      (node (ref "U6") (pin "23") (pinfunction "PTC2_23") (pintype "passive"))
    )
    (net (code "14") (name "/SAT_CTS") (class "Default")
      (node (ref "U8") (pin "P$12") (pinfunction "B1_P$12") (pintype "passive+no_connect"))
    )
    (net (code "15") (name "/SAT_RTS") (class "Default")
      (node (ref "U8") (pin "P$11") (pinfunction "B2_P$11") (pintype "passive"))
    )
    (net (code "16") (name "/SAT_RXD") (class "Default")
      (node (ref "TP24") (pin "TP") (pinfunction "TP_TP") (pintype "passive"))
      (node (ref "U8") (pin "P$9") (pinfunction "B4_P$9") (pintype "passive"))
    )
    (net (code "17") (name "/SAT_TXD") (class "Default")
      (node (ref "TP23") (pin "TP") (pinfunction "TP_TP") (pintype "passive"))
      (node (ref "U8") (pin "P$10") (pinfunction "B3_P$10") (pintype "passive"))
    )
    (net (code "18") (name "/SYS_RESET") (class "Default")
      (node (ref "JRIGHT") (pin "10") (pinfunction "10_10") (pintype "passive"))
      (node (ref "U5") (pin "41") (pinfunction "PTB18_41") (pintype "passive"))
      (node (ref "U6") (pin "19") (pinfunction "RESET_B_PTA20_19") (pintype "passive"))
    )
    (net (code "19") (name "/SYS_SAT_CTS") (class "Default")
      (node (ref "U8") (pin "P$1") (pinfunction "A1_P$1") (pintype "passive"))
    )
    (net (code "20") (name "/SYS_SAT_RTS") (class "Default")
      (node (ref "U8") (pin "P$2") (pinfunction "A2_P$2") (pintype "passive+no_connect"))
    )
    (net (code "21") (name "/SYS_SAT_RX") (class "Default")
      (node (ref "U8") (pin "P$4") (pinfunction "A4_P$4") (pintype "passive"))
    )
    (net (code "22") (name "/SYS_SAT_TX") (class "Default")
      (node (ref "U8") (pin "P$3") (pinfunction "A3_P$3") (pintype "passive"))
    )
    (net (code "23") (name "/SYS_TCK_SWDCLK") (class "Default")
      (node (ref "JRIGHT") (pin "18") (pinfunction "18_18") (pintype "passive"))
      (node (ref "TP17") (pin "TP") (pinfunction "TP_TP") (pintype "passive"))
      (node (ref "U6") (pin "10") (pinfunction "PTA0_10") (pintype "passive"))
    )
    (net (code "24") (name "/SYS_TMS_SWDIO") (class "Default")
      (node (ref "JLEFT") (pin "18") (pinfunction "18_18") (pintype "passive"))
      (node (ref "TP27") (pin "TP") (pinfunction "TP_TP") (pintype "passive"))
      (node (ref "U6") (pin "13") (pinfunction "PTA3_13") (pintype "passive"))
    )
    (net (code "25") (name "/SYS_TX_TO_USR_RX") (class "Default")
      (node (ref "TP25") (pin "TP") (pinfunction "TP_TP") (pintype "passive"))
      (node (ref "U5") (pin "46") (pinfunction "PTC3_46") (pintype "passive"))
      (node (ref "U6") (pin "25") (pinfunction "PTC4_25") (pintype "passive"))
    )
    (net (code "26") (name "/SYS_UBLOX_RX") (class "Default")
      (node (ref "U6") (pin "31") (pinfunction "PTD6_31") (pintype "passive"))
    )
    (net (code "27") (name "/SYS_UBLOX_TX") (class "Default")
      (node (ref "U6") (pin "32") (pinfunction "PTD7_32") (pintype "passive"))
    )
    (net (code "28") (name "/SystemVin") (class "Default")
      (node (ref "C1") (pin "1") (pinfunction "1_1") (pintype "passive"))
      (node (ref "JLEFT") (pin "1") (pinfunction "1_1") (pintype "passive"))
      (node (ref "U1") (pin "17") (pinfunction "CE_17") (pintype "passive"))
      (node (ref "U1") (pin "18") (pinfunction "Vin_18") (pintype "passive"))
      (node (ref "U1") (pin "19") (pinfunction "Vin_19") (pintype "passive"))
      (node (ref "U1") (pin "2") (pinfunction "VPCC_2") (pintype "passive"))
      (node (ref "U1") (pin "3") (pinfunction "SEL_3") (pintype "passive"))
      (node (ref "U1") (pin "4") (pinfunction "PROG2_4") (pintype "passive"))
      (node (ref "U1") (pin "9") (pinfunction "~{TE}_9") (pintype "passive"))
      (node (ref "U3") (pin "CATHODE") (pinfunction "CATHODE_CATHODE") (pintype "passive"))
    )
    (net (code "29") (name "/TXL_ON_N") (class "Default")
      (node (ref "U6") (pin "1") (pinfunction "PTE0_1") (pintype "passive"))
      (node (ref "U9") (pin "4") (pinfunction "ON_4") (pintype "passive"))
    )
    (net (code "30") (name "/TXL_VCC") (class "Default")
      (node (ref "C26") (pin "1") (pinfunction "1_1") (pintype "passive"))
      (node (ref "U8") (pin "P$14") (pinfunction "VCCA_P$14") (pintype "power_in"))
      (node (ref "U8") (pin "P$15") (pinfunction "DIR1_P$15") (pintype "passive"))
      (node (ref "U8") (pin "P$5") (pinfunction "DIR3_P$5") (pintype "passive"))
      (node (ref "U9") (pin "1") (pinfunction "VOUT_1") (pintype "passive"))
    )
    (net (code "31") (name "/UBLOX_1.8V_SUPPLY") (class "Default")
      (node (ref "C25") (pin "1") (pinfunction "1_1") (pintype "passive"))
      (node (ref "U8") (pin "P$13") (pinfunction "VCCB_P$13") (pintype "power_in"))
    )
    (net (code "32") (name "/UBLOX_PWR_ON") (class "Default")
      (node (ref "U6") (pin "14") (pinfunction "PTA4_14") (pintype "passive"))
    )
    (net (code "33") (name "/UBLOX_RESET_N") (class "Default")
      (node (ref "U6") (pin "11") (pinfunction "PTA1_11") (pintype "passive"))
    )
    (net (code "34") (name "/UBLOX_VCC") (class "Default")
      (node (ref "C39") (pin "1") (pinfunction "1_1") (pintype "passive"))
      (node (ref "C40") (pin "1") (pinfunction "1_1") (pintype "passive"))
      (node (ref "C46") (pin "1") (pinfunction "1_1") (pintype "passive"))
      (node (ref "C47") (pin "1") (pinfunction "1_1") (pintype "passive"))
      (node (ref "C6") (pin "1") (pinfunction "1_1") (pintype "passive"))
      (node (ref "L7") (pin "1") (pinfunction "P$1_1") (pintype "passive"))
      (node (ref "TP28") (pin "TP") (pinfunction "TP_TP") (pintype "passive"))
    )
    (net (code "35") (name "/USB_5V") (class "Default")
      (node (ref "F6") (pin "1") (pinfunction "P$1_1") (pintype "passive"))
      (node (ref "J1") (pin "VCC") (pinfunction "VBUS_VCC") (pintype "passive"))
      (node (ref "TP1") (pin "TP") (pinfunction "TP_TP") (pintype "passive"))
    )
    (net (code "36") (name "/USB_D_N") (class "Default")
      (node (ref "D5") (pin "2") (pinfunction "2_2") (pintype "passive"))
      (node (ref "R1") (pin "2") (pinfunction "2_2") (pintype "passive"))
      (node (ref "U5") (pin "6") (pinfunction "USB0_DM_6") (pintype "passive"))
    )
    (net (code "37") (name "/USB_D_P") (class "Default")
      (node (ref "D4") (pin "2") (pinfunction "2_2") (pintype "passive"))
      (node (ref "R2") (pin "2") (pinfunction "2_2") (pintype "passive"))
      (node (ref "U5") (pin "5") (pinfunction "USB0_DP_5") (pintype "passive"))
    )
    (net (code "38") (name "/USB_ID") (class "Default")
      (node (ref "J1") (pin "ID") (pinfunction "ID_ID") (pintype "passive"))
      (node (ref "R66") (pin "1") (pinfunction "1_1") (pintype "passive"))
    )
    (net (code "39") (name "/USB_IN") (class "Default")
      (node (ref "C11") (pin "1") (pinfunction "1_1") (pintype "passive"))
      (node (ref "C12") (pin "1") (pinfunction "1_1") (pintype "passive"))
      (node (ref "D3") (pin "2") (pinfunction "2_2") (pintype "passive"))
      (node (ref "F6") (pin "2") (pinfunction "P$2_2") (pintype "passive"))
      (node (ref "L2") (pin "2") (pinfunction "P$2_2") (pintype "passive"))
      (node (ref "TP5") (pin "TP") (pinfunction "TP_TP") (pintype "passive"))
      (node (ref "U3") (pin "ANODE") (pinfunction "ANODE_ANODE") (pintype "passive"))
    )
    (net (code "40") (name "/USB_IN_D_N") (class "Default")
      (node (ref "J1") (pin "D-") (pinfunction "D-_D-") (pintype "passive"))
      (node (ref "R1") (pin "1") (pinfunction "1_1") (pintype "passive"))
    )
    (net (code "41") (name "/USB_IN_D_P") (class "Default")
      (node (ref "J1") (pin "D+") (pinfunction "D+_D+") (pintype "passive"))
      (node (ref "R2") (pin "1") (pinfunction "1_1") (pintype "passive"))
    )
    (net (code "42") (name "/USER01") (class "Default")
      (node (ref "JLEFT") (pin "12") (pinfunction "12_12") (pintype "passive"))
      (node (ref "U5") (pin "29") (pinfunction "PTA13_29") (pintype "passive"))
    )
    (net (code "43") (name "/USER02") (class "Default")
      (node (ref "JLEFT") (pin "11") (pinfunction "11_11") (pintype "passive"))
      (node (ref "U5") (pin "28") (pinfunction "PTA12_28") (pintype "passive"))
    )
    (net (code "44") (name "/USER03") (class "Default")
      (node (ref "JLEFT") (pin "10") (pinfunction "10_10") (pintype "passive"))
      (node (ref "U5") (pin "27") (pinfunction "PTA5_27") (pintype "passive"))
    )
    (net (code "45") (name "/USER04") (class "Default")
      (node (ref "JLEFT") (pin "3") (pinfunction "3_3") (pintype "passive"))
      (node (ref "U5") (pin "1") (pinfunction "PTE0_1") (pintype "passive"))
    )
    (net (code "46") (name "/USER05") (class "Default")
      (node (ref "JLEFT") (pin "4") (pinfunction "4_4") (pintype "passive"))
      (node (ref "U5") (pin "2") (pinfunction "PTE1_2") (pintype "passive"))
    )
    (net (code "47") (name "/USER06") (class "Default")
      (node (ref "JLEFT") (pin "13") (pinfunction "13_13") (pintype "passive"))
      (node (ref "U5") (pin "35") (pinfunction "PTB0_35") (pintype "passive"))
    )
    (net (code "48") (name "/USER07") (class "Default")
      (node (ref "JLEFT") (pin "9") (pinfunction "9_9") (pintype "passive"))
      (node (ref "U5") (pin "36") (pinfunction "PTB1_36") (pintype "passive"))
    )
    (net (code "49") (name "/USER08") (class "Default")
      (node (ref "JLEFT") (pin "14") (pinfunction "14_14") (pintype "passive"))
      (node (ref "U5") (pin "18") (pinfunction "DAC0_OUT_18") (pintype "passive"))
    )
    (net (code "50") (name "/USER09") (class "Default")
      (node (ref "JRIGHT") (pin "8") (pinfunction "8_8") (pintype "passive"))
      (node (ref "U5") (pin "45") (pinfunction "PTC2_45") (pintype "passive"))
    )
    (net (code "51") (name "/USER10") (class "Default")
      (node (ref "JRIGHT") (pin "7") (pinfunction "7_7") (pintype "passive"))
      (node (ref "U5") (pin "44") (pinfunction "PTC1_44") (pintype "passive"))
    )
    (net (code "52") (name "/USER11") (class "Default")
      (node (ref "JRIGHT") (pin "9") (pinfunction "9_9") (pintype "passive"))
      (node (ref "U5") (pin "43") (pinfunction "PTC0_43") (pintype "passive"))
    )
    (net (code "53") (name "/USER12") (class "Default")
      (node (ref "JRIGHT") (pin "6") (pinfunction "6_6") (pintype "passive"))
      (node (ref "U5") (pin "53") (pinfunction "PTC8_53") (pintype "passive"))
    )
    (net (code "54") (name "/USER13") (class "Default")
      (node (ref "JLEFT") (pin "5") (pinfunction "5_5") (pintype "passive"))
      (node (ref "U5") (pin "58") (pinfunction "PTD1_58") (pintype "passive"))
    )
    (net (code "55") (name "/USER14") (class "Default")
      (node (ref "JLEFT") (pin "6") (pinfunction "6_6") (pintype "passive"))
      (node (ref "U5") (pin "59") (pinfunction "PTD2_59") (pintype "passive"))
    )
    (net (code "56") (name "/USER15") (class "Default")
      (node (ref "JLEFT") (pin "8") (pinfunction "8_8") (pintype "passive"))
      (node (ref "U5") (pin "60") (pinfunction "PTD3_60") (pintype "passive"))
    )
    (net (code "57") (name "/USER16") (class "Default")
      (node (ref "JRIGHT") (pin "4") (pinfunction "4_4") (pintype "passive"))
      (node (ref "U5") (pin "61") (pinfunction "PTD4_61") (pintype "passive"))
    )
    (net (code "58") (name "/USER17") (class "Default")
      (node (ref "JLEFT") (pin "7") (pinfunction "7_7") (pintype "passive"))
      (node (ref "U5") (pin "62") (pinfunction "PTD5_62") (pintype "passive"))
    )
    (net (code "59") (name "/USER18") (class "Default")
      (node (ref "JRIGHT") (pin "5") (pinfunction "5_5") (pintype "passive"))
      (node (ref "U5") (pin "63") (pinfunction "PTD6_63") (pintype "passive"))
    )
    (net (code "60") (name "/USER19") (class "Default")
      (node (ref "JRIGHT") (pin "3") (pinfunction "3_3") (pintype "passive"))
      (node (ref "U5") (pin "64") (pinfunction "PTD7_64") (pintype "passive"))
    )
    (net (code "61") (name "/USER23") (class "Default")
      (node (ref "JRIGHT") (pin "13") (pinfunction "13_13") (pintype "passive"))
      (node (ref "U5") (pin "51") (pinfunction "PTC6_51") (pintype "passive"))
    )
    (net (code "62") (name "/USER24") (class "Default")
      (node (ref "JRIGHT") (pin "14") (pinfunction "14_14") (pintype "passive"))
      (node (ref "U5") (pin "52") (pinfunction "PTC7_52") (pintype "passive"))
    )
    (net (code "63") (name "/USER26") (class "Default")
      (node (ref "JRIGHT") (pin "15") (pinfunction "15_15") (pintype "passive"))
      (node (ref "U5") (pin "55") (pinfunction "PTC10_55") (pintype "passive"))
    )
    (net (code "64") (name "/USER27") (class "Default")
      (node (ref "JRIGHT") (pin "17") (pinfunction "17_17") (pintype "passive"))
      (node (ref "U5") (pin "56") (pinfunction "PTC11_56") (pintype "passive"))
    )
    (net (code "65") (name "/USER28") (class "Default")
      (node (ref "JRIGHT") (pin "16") (pinfunction "16_16") (pintype "passive"))
      (node (ref "U5") (pin "57") (pinfunction "PTD0_57") (pintype "passive"))
    )
    (net (code "66") (name "/USER_PROGRAM") (class "Default")
      (node (ref "JRIGHT") (pin "11") (pinfunction "11_11") (pintype "passive"))
      (node (ref "R24") (pin "1") (pinfunction "1_1") (pintype "passive"))
      (node (ref "SW2") (pin "1") (pinfunction "P$1_1") (pintype "passive"))
      (node (ref "SW2") (pin "2") (pinfunction "P$1_2") (pintype "passive"))
      (node (ref "U5") (pin "54") (pinfunction "PTC9_54") (pintype "passive"))
      (node (ref "U6") (pin "27") (pinfunction "PTC6_27") (pintype "passive"))
    )
    (net (code "67") (name "/USR_LED") (class "Default")
      (node (ref "D1") (pin "ANODE") (pinfunction "ANODE_ANODE") (pintype "passive"))
      (node (ref "U5") (pin "42") (pinfunction "PTB19_42") (pintype "passive"))
    )
    (net (code "68") (name "/USR_RESET") (class "Default")
      (node (ref "C24") (pin "1") (pinfunction "1_1") (pintype "passive"))
      (node (ref "JLEFT") (pin "15") (pinfunction "15_15") (pintype "passive"))
      (node (ref "R47") (pin "1") (pinfunction "1_1") (pintype "passive"))
      (node (ref "SW1") (pin "1") (pinfunction "P$1_1") (pintype "passive"))
      (node (ref "SW1") (pin "2") (pinfunction "P$1_2") (pintype "passive"))
      (node (ref "U5") (pin "34") (pinfunction "RESET_B_34") (pintype "passive"))
      (node (ref "U6") (pin "26") (pinfunction "PTC5_26") (pintype "passive"))
    )
    (net (code "69") (name "/USR_TCK_SWDCLK") (class "Default")
      (node (ref "JLEFT") (pin "17") (pinfunction "17_17") (pintype "passive"))
      (node (ref "U5") (pin "22") (pinfunction "PTA0_22") (pintype "passive"))
      (node (ref "U6") (pin "4") (pinfunction "PTE17_4") (pintype "passive"))
    )
    (net (code "70") (name "/USR_TDI") (class "Default")
      (node (ref "R66") (pin "2") (pinfunction "2_2") (pintype "passive"))
      (node (ref "U5") (pin "23") (pinfunction "PTA1_23") (pintype "passive"))
      (node (ref "U6") (pin "5") (pinfunction "PTE18_5") (pintype "passive"))
    )
    (net (code "71") (name "/USR_TDO_SWO") (class "Default")
      (node (ref "U5") (pin "24") (pinfunction "PTA2_24") (pintype "passive"))
      (node (ref "U6") (pin "6") (pinfunction "PTE19_6") (pintype "passive"))
    )
    (net (code "72") (name "/USR_TMS_SWDIO") (class "Default")
      (node (ref "JLEFT") (pin "16") (pinfunction "16_16") (pintype "passive"))
      (node (ref "U5") (pin "25") (pinfunction "PTA3_25") (pintype "passive"))
      (node (ref "U6") (pin "22") (pinfunction "PTC1_22") (pintype "passive"))
    )
    (net (code "73") (name "/USR_TX_TO_SYS_RX") (class "Default")
      (node (ref "TP26") (pin "TP") (pinfunction "TP_TP") (pintype "passive"))
      (node (ref "U5") (pin "49") (pinfunction "PTC4_49") (pintype "passive"))
      (node (ref "U6") (pin "24") (pinfunction "PTC3_24") (pintype "passive"))
    )
    (net (code "74") (name "/VBATT") (class "Default")
      (node (ref "J2") (pin "BAT") (pinfunction "BAT_BAT") (pintype "passive"))
      (node (ref "R45") (pin "2") (pinfunction "2_2") (pintype "passive"))
      (node (ref "TP13") (pin "TP") (pinfunction "TP_TP") (pintype "passive"))
      (node (ref "U1") (pin "14") (pinfunction "Vbat_14") (pintype "passive"))
      (node (ref "U1") (pin "15") (pinfunction "Vbat_15") (pintype "passive"))
      (node (ref "U1") (pin "16") (pinfunction "Vbat_16") (pintype "passive"))
    )
    (net (code "75") (name "/VOUT33") (class "Default")
      (node (ref "C10") (pin "1") (pinfunction "1_1") (pintype "passive"))
      (node (ref "U5") (pin "7") (pinfunction "VOUT33_7") (pintype "passive"))
    )
    (net (code "76") (name "/VREGIN") (class "Default")
      (node (ref "C18") (pin "1") (pinfunction "1_1") (pintype "passive"))
      (node (ref "U4") (pin "CATHODE") (pinfunction "CATHODE_CATHODE") (pintype "passive"))
      (node (ref "U5") (pin "8") (pinfunction "VREGIN_8") (pintype "passive"))
    )
    (net (code "77") (name "/VSystem") (class "Default")
      (node (ref "C33") (pin "1") (pinfunction "1_1") (pintype "passive"))
      (node (ref "C34") (pin "1") (pinfunction "1_1") (pintype "passive"))
      (node (ref "D8") (pin "ANODE") (pinfunction "ANODE_ANODE") (pintype "passive"))
      (node (ref "U1") (pin "1") (pinfunction "OUT_1") (pintype "passive"))
      (node (ref "U1") (pin "20") (pinfunction "OUT_20") (pintype "passive"))
      (node (ref "U2") (pin "10") (pinfunction "VIN_10") (pintype "passive"))
      (node (ref "U2") (pin "11") (pinfunction "VIN_11") (pintype "passive"))
    )
    (net (code "78") (name "/VSystem_User") (class "Default")
      (node (ref "D8") (pin "CATHODE") (pinfunction "CATHODE_CATHODE") (pintype "passive"))
      (node (ref "JRIGHT") (pin "1") (pinfunction "1_1") (pintype "passive"))
    )
    (net (code "79") (name "/WAKE_USR") (class "Default")
      (node (ref "D7") (pin "ANODE") (pinfunction "ANODE_ANODE") (pintype "passive"))
      (node (ref "U5") (pin "50") (pinfunction "PTC5_50") (pintype "passive"))
      (node (ref "U6") (pin "28") (pinfunction "PTC7_28") (pintype "passive"))
    )
    (net (code "80") (name "GND") (class "Default")
      (node (ref "C1") (pin "2") (pinfunction "2_2") (pintype "passive"))
      (node (ref "C10") (pin "2") (pinfunction "2_2") (pintype "passive"))
      (node (ref "C11") (pin "2") (pinfunction "2_2") (pintype "passive"))
      (node (ref "C12") (pin "2") (pinfunction "2_2") (pintype "passive"))
      (node (ref "C16") (pin "2") (pinfunction "2_2") (pintype "passive"))
      (node (ref "C18") (pin "2") (pinfunction "2_2") (pintype "passive"))
      (node (ref "C20") (pin "2") (pinfunction "2_2") (pintype "passive"))
      (node (ref "C24") (pin "2") (pinfunction "2_2") (pintype "passive"))
      (node (ref "C25") (pin "2") (pinfunction "2_2") (pintype "passive"))
      (node (ref "C26") (pin "2") (pinfunction "2_2") (pintype "passive"))
      (node (ref "C27") (pin "2") (pinfunction "2_2") (pintype "passive"))
      (node (ref "C28") (pin "2") (pinfunction "2_2") (pintype "passive"))
      (node (ref "C3") (pin "2") (pinfunction "2_2") (pintype "passive"))
      (node (ref "C33") (pin "2") (pinfunction "2_2") (pintype "passive"))
      (node (ref "C34") (pin "2") (pinfunction "2_2") (pintype "passive"))
      (node (ref "C36") (pin "2") (pinfunction "2_2") (pintype "passive"))
      (node (ref "C37") (pin "2") (pinfunction "2_2") (pintype "passive"))
      (node (ref "C38") (pin "2") (pinfunction "2_2") (pintype "passive"))
      (node (ref "C39") (pin "2") (pinfunction "2_2") (pintype "passive"))
      (node (ref "C4") (pin "2") (pinfunction "2_2") (pintype "passive"))
      (node (ref "C40") (pin "2") (pinfunction "2_2") (pintype "passive"))
      (node (ref "C46") (pin "2") (pinfunction "2_2") (pintype "passive"))
      (node (ref "C47") (pin "2") (pinfunction "2_2") (pintype "passive"))
      (node (ref "C48") (pin "2") (pinfunction "2_2") (pintype "passive"))
      (node (ref "C49") (pin "2") (pinfunction "2_2") (pintype "passive"))
      (node (ref "C6") (pin "2") (pinfunction "2_2") (pintype "passive"))
      (node (ref "C7") (pin "2") (pinfunction "2_2") (pintype "passive"))
      (node (ref "C8") (pin "2") (pinfunction "2_2") (pintype "passive"))
      (node (ref "C9") (pin "2") (pinfunction "2_2") (pintype "passive"))
      (node (ref "D3") (pin "1") (pinfunction "1_1") (pintype "passive"))
      (node (ref "D4") (pin "1") (pinfunction "1_1") (pintype "passive"))
      (node (ref "D5") (pin "1") (pinfunction "1_1") (pintype "passive"))
      (node (ref "J1") (pin "GND") (pinfunction "GND_GND") (pintype "passive"))
      (node (ref "J2") (pin "CHASSIS1") (pinfunction "CHASSIS_1_CHASSIS1") (pintype "passive"))
      (node (ref "J2") (pin "CHASSIS2") (pinfunction "CHASSIS_2_CHASSIS2") (pintype "passive"))
      (node (ref "J2") (pin "GND") (pinfunction "GND_GND") (pintype "passive"))
      (node (ref "JLEFT") (pin "2") (pinfunction "2_2") (pintype "passive"))
      (node (ref "JRIGHT") (pin "2") (pinfunction "2_2") (pintype "passive"))
      (node (ref "L3") (pin "2") (pinfunction "P$2_2") (pintype "passive"))
      (node (ref "R12") (pin "2") (pinfunction "2_2") (pintype "passive"))
      (node (ref "R2000") (pin "1") (pinfunction "1_1") (pintype "passive"))
      (node (ref "R26") (pin "1") (pinfunction "1_1") (pintype "passive"))
      (node (ref "R65") (pin "1") (pinfunction "1_1") (pintype "passive"))
      (node (ref "R7") (pin "1") (pinfunction "1_1") (pintype "passive"))
      (node (ref "R8") (pin "1") (pinfunction "1_1") (pintype "passive"))
      (node (ref "SW1") (pin "3") (pinfunction "P$1_3") (pintype "passive"))
      (node (ref "SW1") (pin "4") (pinfunction "P$2_4") (pintype "passive"))
      (node (ref "SW2") (pin "3") (pinfunction "P$1_3") (pintype "passive"))
      (node (ref "SW2") (pin "4") (pinfunction "P$2_4") (pintype "passive"))
      (node (ref "U1") (pin "10") (pinfunction "Vss_10") (pintype "passive"))
      (node (ref "U1") (pin "11") (pinfunction "Vss_11") (pintype "passive"))
      (node (ref "U1") (pin "21") (pinfunction "Vss_21") (pintype "passive"))
      (node (ref "U19") (pin "1") (pinfunction "CTG_1") (pintype "passive"))
      (node (ref "U19") (pin "4") (pinfunction "GND_4") (pintype "passive"))
      (node (ref "U19") (pin "6") (pinfunction "QST_6") (pintype "passive"))
      (node (ref "U19") (pin "EP") (pinfunction "GND_EP") (pintype "passive"))
      (node (ref "U2") (pin "13") (pinfunction "PS/SYNC_13") (pintype "passive"))
      (node (ref "U2") (pin "2") (pinfunction "GND_2") (pintype "passive"))
      (node (ref "U2") (pin "POWERPAD") (pinfunction "PGND_POWERPAD") (pintype "passive"))
      (node (ref "U5") (pin "31") (pinfunction "VSS_31") (pintype "passive"))
      (node (ref "U5") (pin "4") (pinfunction "VSS_4") (pintype "passive"))
      (node (ref "U5") (pin "47") (pinfunction "VSS_47") (pintype "passive"))
      (node (ref "U6") (pin "16") (pinfunction "VSS_16") (pintype "passive"))
      (node (ref "U6") (pin "8") (pinfunction "VSSA_8") (pintype "passive"))
      (node (ref "U6") (pin "PAD") (pinfunction "VSS_PAD") (pintype "passive"))
      (node (ref "U7") (pin "2") (pinfunction "GND_2") (pintype "passive"))
      (node (ref "U7") (pin "5") (pinfunction "GND_5") (pintype "passive"))
      (node (ref "U8") (pin "P$16") (pinfunction "DIR2_P$16") (pintype "passive"))
      (node (ref "U8") (pin "P$6") (pinfunction "DIR4_P$6") (pintype "passive"))
      (node (ref "U8") (pin "P$7") (pinfunction "~OE_P$7") (pintype "passive"))
      (node (ref "U8") (pin "P$8") (pinfunction "GND_P$8") (pintype "passive"))
      (node (ref "U9") (pin "2") (pinfunction "GND_2") (pintype "passive"))
      (node (ref "X1") (pin "2") (pinfunction "2_2") (pintype "passive"))
      (node (ref "X1") (pin "4") (pinfunction "2_4") (pintype "passive"))
    )
    (net (code "81") (name "Net-(D1-PadCATHODE)") (class "Default")
      (node (ref "D1") (pin "CATHODE") (pinfunction "CATHODE_CATHODE") (pintype "passive"))
      (node (ref "R26") (pin "2") (pinfunction "2_2") (pintype "passive"))
    )
    (net (code "82") (name "Net-(D2-CATHODE_B)") (class "Default")
      (node (ref "D2") (pin "3") (pinfunction "CATHODE_B_3") (pintype "passive"))
      (node (ref "R21") (pin "2") (pinfunction "2_2") (pintype "passive"))
    )
    (net (code "83") (name "Net-(D2-CATHODE_G)") (class "Default")
      (node (ref "D2") (pin "4") (pinfunction "CATHODE_G_4") (pintype "passive"))
      (node (ref "R22") (pin "2") (pinfunction "2_2") (pintype "passive"))
    )
    (net (code "84") (name "Net-(D2-CATHODE_R)") (class "Default")
      (node (ref "D2") (pin "2") (pinfunction "CATHODE_R_2") (pintype "passive"))
      (node (ref "R20") (pin "2") (pinfunction "2_2") (pintype "passive"))
    )
    (net (code "85") (name "Net-(D7-PadCATHODE)") (class "Default")
      (node (ref "D7") (pin "CATHODE") (pinfunction "CATHODE_CATHODE") (pintype "passive"))
      (node (ref "R65") (pin "2") (pinfunction "2_2") (pintype "passive"))
    )
    (net (code "86") (name "Net-(L1-P$2)") (class "Default")
      (node (ref "C13") (pin "1") (pinfunction "1_1") (pintype "passive"))
      (node (ref "L1") (pin "2") (pinfunction "P$2_2") (pintype "passive"))
      (node (ref "R19") (pin "1") (pinfunction "1_1") (pintype "passive"))
      (node (ref "U5") (pin "13") (pinfunction "VDDA_13") (pintype "passive"))
    )
    (net (code "87") (name "Net-(L2-P$1)") (class "Default")
      (node (ref "L2") (pin "1") (pinfunction "P$1_1") (pintype "passive"))
      (node (ref "U4") (pin "ANODE") (pinfunction "ANODE_ANODE") (pintype "passive"))
    )
    (net (code "88") (name "Net-(L5-PadP$1)") (class "Default")
      (node (ref "L5") (pin "P$1") (pinfunction "P$1_P$1") (pintype "passive"))
      (node (ref "U2") (pin "8") (pinfunction "L1_8") (pintype "passive"))
      (node (ref "U2") (pin "9") (pinfunction "L1_9") (pintype "passive"))
    )
    (net (code "89") (name "Net-(L5-PadP$2)") (class "Default")
      (node (ref "L5") (pin "P$2") (pinfunction "P$2_P$2") (pintype "passive"))
      (node (ref "U2") (pin "6") (pinfunction "L2_6") (pintype "passive"))
      (node (ref "U2") (pin "7") (pinfunction "L2_7") (pintype "passive"))
    )
    (net (code "90") (name "Net-(U1-PROG1)") (class "Default")
      (node (ref "R8") (pin "2") (pinfunction "2_2") (pintype "passive"))
      (node (ref "U1") (pin "13") (pinfunction "PROG1_13") (pintype "passive"))
    )
    (net (code "91") (name "Net-(U1-PROG3)") (class "Default")
      (node (ref "R7") (pin "2") (pinfunction "2_2") (pintype "passive"))
      (node (ref "U1") (pin "12") (pinfunction "PROG3_12") (pintype "passive"))
    )
    (net (code "92") (name "Net-(U1-Therm)") (class "Default")
      (node (ref "R2000") (pin "2") (pinfunction "2_2") (pintype "passive"))
      (node (ref "U1") (pin "5") (pinfunction "Therm_5") (pintype "passive"))
    )
    (net (code "93") (name "Net-(U2-EN)") (class "Default")
      (node (ref "C48") (pin "1") (pinfunction "1_1") (pintype "passive"))
      (node (ref "U2") (pin "1") (pinfunction "VINA_1") (pintype "passive"))
      (node (ref "U2") (pin "12") (pinfunction "EN_12") (pintype "passive"))
    )
    (net (code "94") (name "Net-(U2-FB)") (class "Default")
      (node (ref "R12") (pin "1") (pinfunction "1_1") (pintype "passive"))
      (node (ref "R3") (pin "1") (pinfunction "1_1") (pintype "passive"))
      (node (ref "U2") (pin "3") (pinfunction "FB_3") (pintype "passive"))
    )
    (net (code "95") (name "Net-(U5-EXTAL32)") (class "Default")
      (node (ref "U5") (pin "20") (pinfunction "EXTAL32_20") (pintype "passive"))
      (node (ref "X2") (pin "1") (pinfunction "XTAL1_1") (pintype "passive"))
    )
    (net (code "96") (name "Net-(U5-PTA18)") (class "Default")
      (node (ref "U5") (pin "32") (pinfunction "PTA18_32") (pintype "passive"))
      (node (ref "X1") (pin "1") (pinfunction "1_1") (pintype "passive"))
    )
    (net (code "97") (name "Net-(U5-PTA19)") (class "Default")
      (node (ref "U5") (pin "33") (pinfunction "PTA19_33") (pintype "passive"))
      (node (ref "X1") (pin "3") (pinfunction "3_3") (pintype "passive"))
    )
    (net (code "98") (name "Net-(U5-VREF_OUT)") (class "Default")
      (node (ref "C15") (pin "1") (pinfunction "1_1") (pintype "passive"))
      (node (ref "U5") (pin "17") (pinfunction "VREF_OUT_17") (pintype "passive"))
    )
    (net (code "99") (name "Net-(U5-XTAL32)") (class "Default")
      (node (ref "U5") (pin "19") (pinfunction "XTAL32_19") (pintype "passive"))
      (node (ref "X2") (pin "2") (pinfunction "XTAL2_2") (pintype "passive"))
    )
    (net (code "100") (name "Net-(U6-PTA18)") (class "Default")
      (node (ref "U6") (pin "17") (pinfunction "PTA18_17") (pintype "passive"))
      (node (ref "X3") (pin "2") (pinfunction "XTAL2_2") (pintype "passive"))
    )
    (net (code "101") (name "Net-(U6-PTA19)") (class "Default")
      (node (ref "U6") (pin "18") (pinfunction "PTA19_18") (pintype "passive"))
      (node (ref "X3") (pin "1") (pinfunction "XTAL1_1") (pintype "passive"))
    )
    (net (code "102") (name "Net-(U19-CELL)") (class "Default")
      (node (ref "C20") (pin "1") (pinfunction "1_1") (pintype "passive"))
      (node (ref "R45") (pin "1") (pinfunction "1_1") (pintype "passive"))
      (node (ref "U19") (pin "2") (pinfunction "CELL_2") (pintype "passive"))
    )
    (net (code "103") (name "unconnected-(U2-PG-Pad14)") (class "Default")
      (node (ref "U2") (pin "14") (pinfunction "PG_14") (pintype "passive"))
    )
    (net (code "104") (name "unconnected-(U5-PGA0_DM-Pad10)") (class "Default")
      (node (ref "U5") (pin "10") (pinfunction "PGA0_DM_10") (pintype "passive"))
    )
    (net (code "105") (name "unconnected-(U5-PGA0_DP-Pad9)") (class "Default")
      (node (ref "U5") (pin "9") (pinfunction "PGA0_DP_9") (pintype "passive"))
    )
    (net (code "106") (name "unconnected-(U5-PGA1_DM-Pad12)") (class "Default")
      (node (ref "U5") (pin "12") (pinfunction "PGA1_DM_12") (pintype "passive"))
    )
    (net (code "107") (name "unconnected-(U5-PGA1_DP-Pad11)") (class "Default")
      (node (ref "U5") (pin "11") (pinfunction "PGA1_DP_11") (pintype "passive"))
    )
    (net (code "108") (name "unconnected-(U5-PTB16-Pad39)") (class "Default")
      (node (ref "U5") (pin "39") (pinfunction "PTB16_39") (pintype "passive"))
    )
    (net (code "109") (name "unconnected-(U5-PTB17-Pad40)") (class "Default")
      (node (ref "U5") (pin "40") (pinfunction "PTB17_40") (pintype "passive"))
    )
    (net (code "110") (name "unconnected-(U9-OC-Pad3)") (class "Default")
      (node (ref "U9") (pin "3") (pinfunction "OC_3") (pintype "passive+no_connect"))
    )
    (net (code "111") (name "unconnected-(U19-ALT-Pad5)") (class "Default")
      (node (ref "U19") (pin "5") (pinfunction "ALT_5") (pintype "passive"))
    )
  )
)
